# EEZ_CF-DIC_r5B6.net
KiCad netlist of a schematic drawn in EAGLE
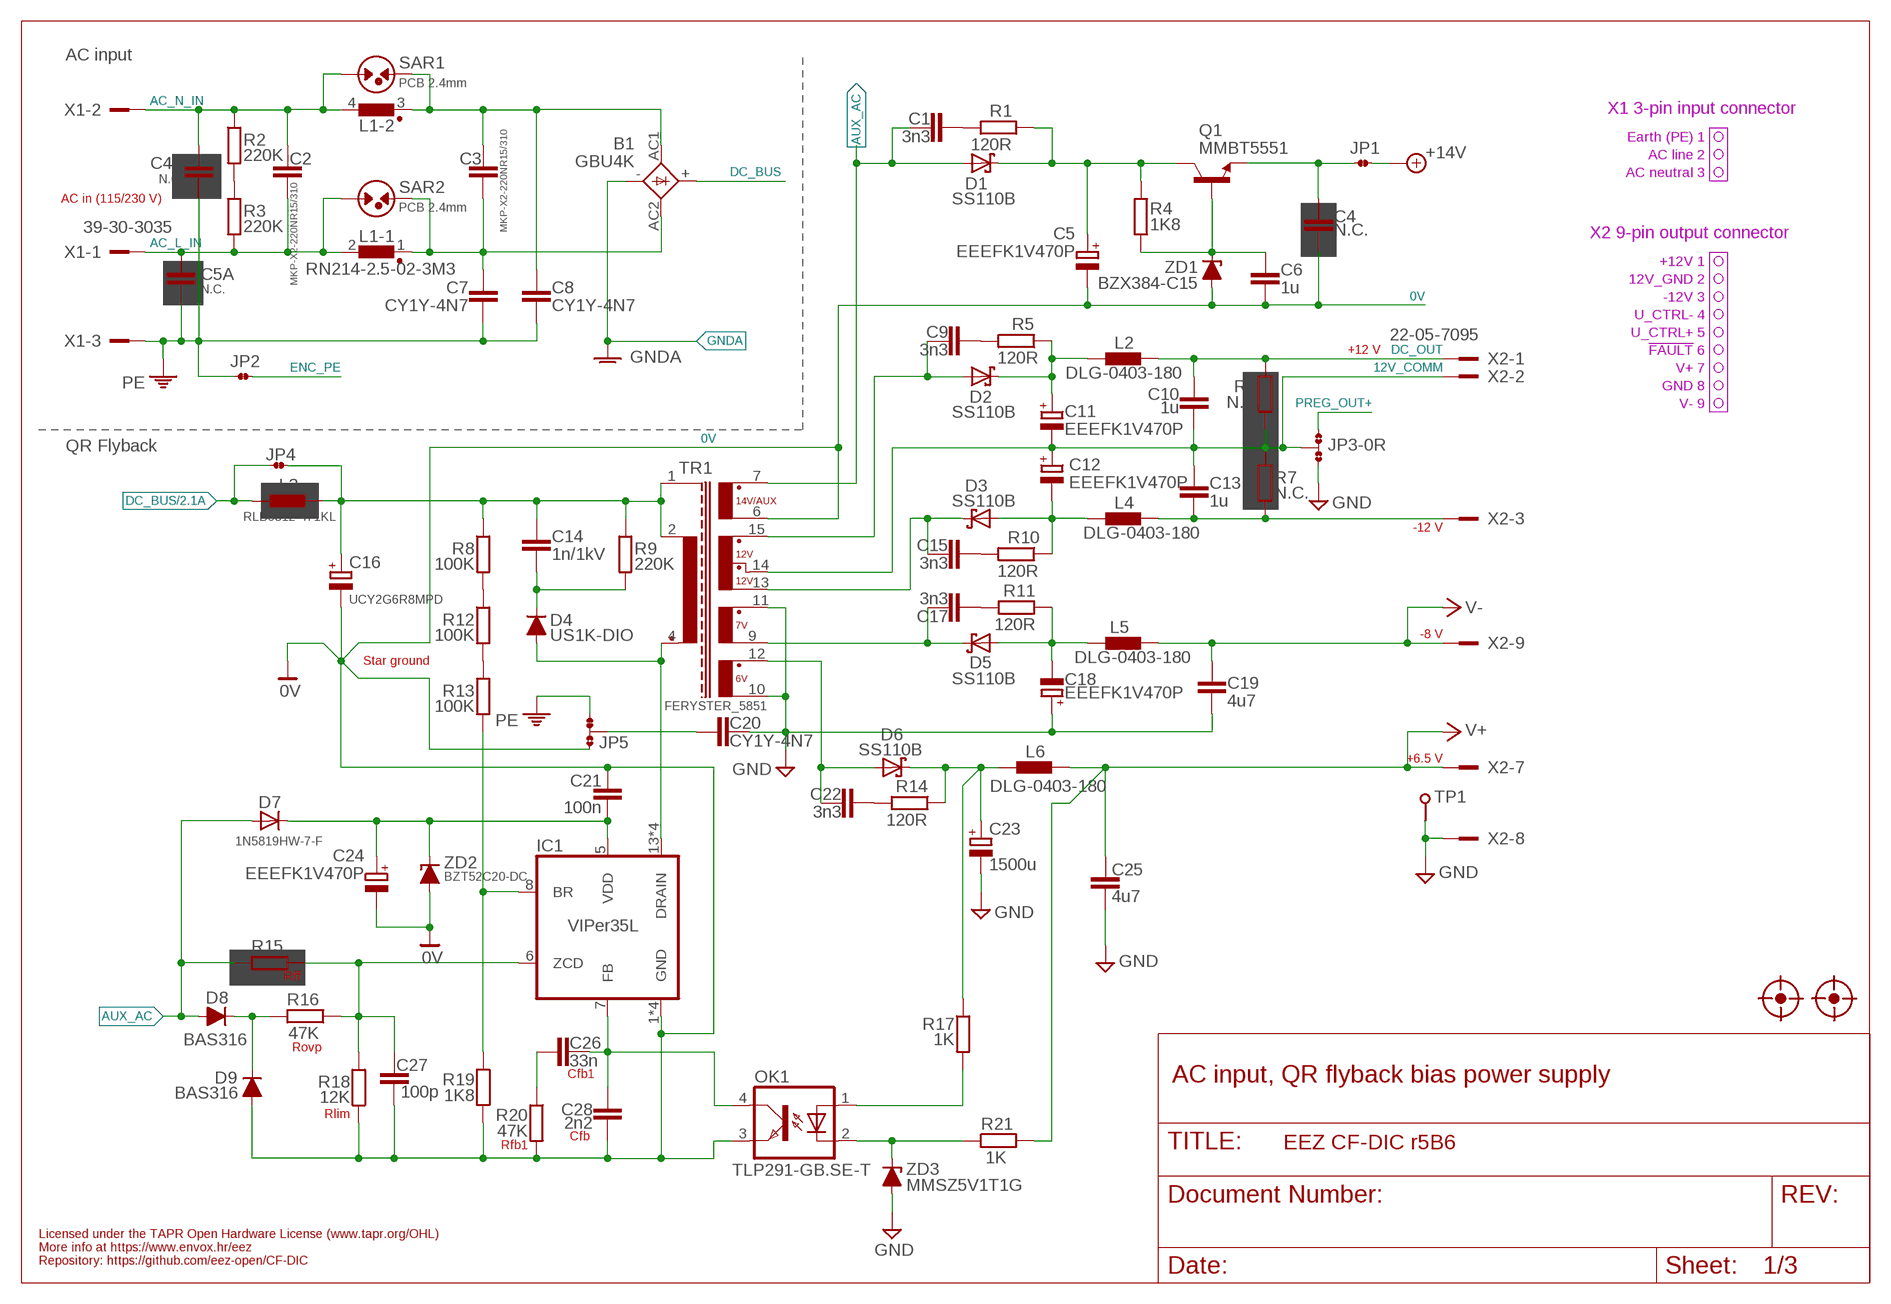
[diagram p0: schematic, sheet 1]
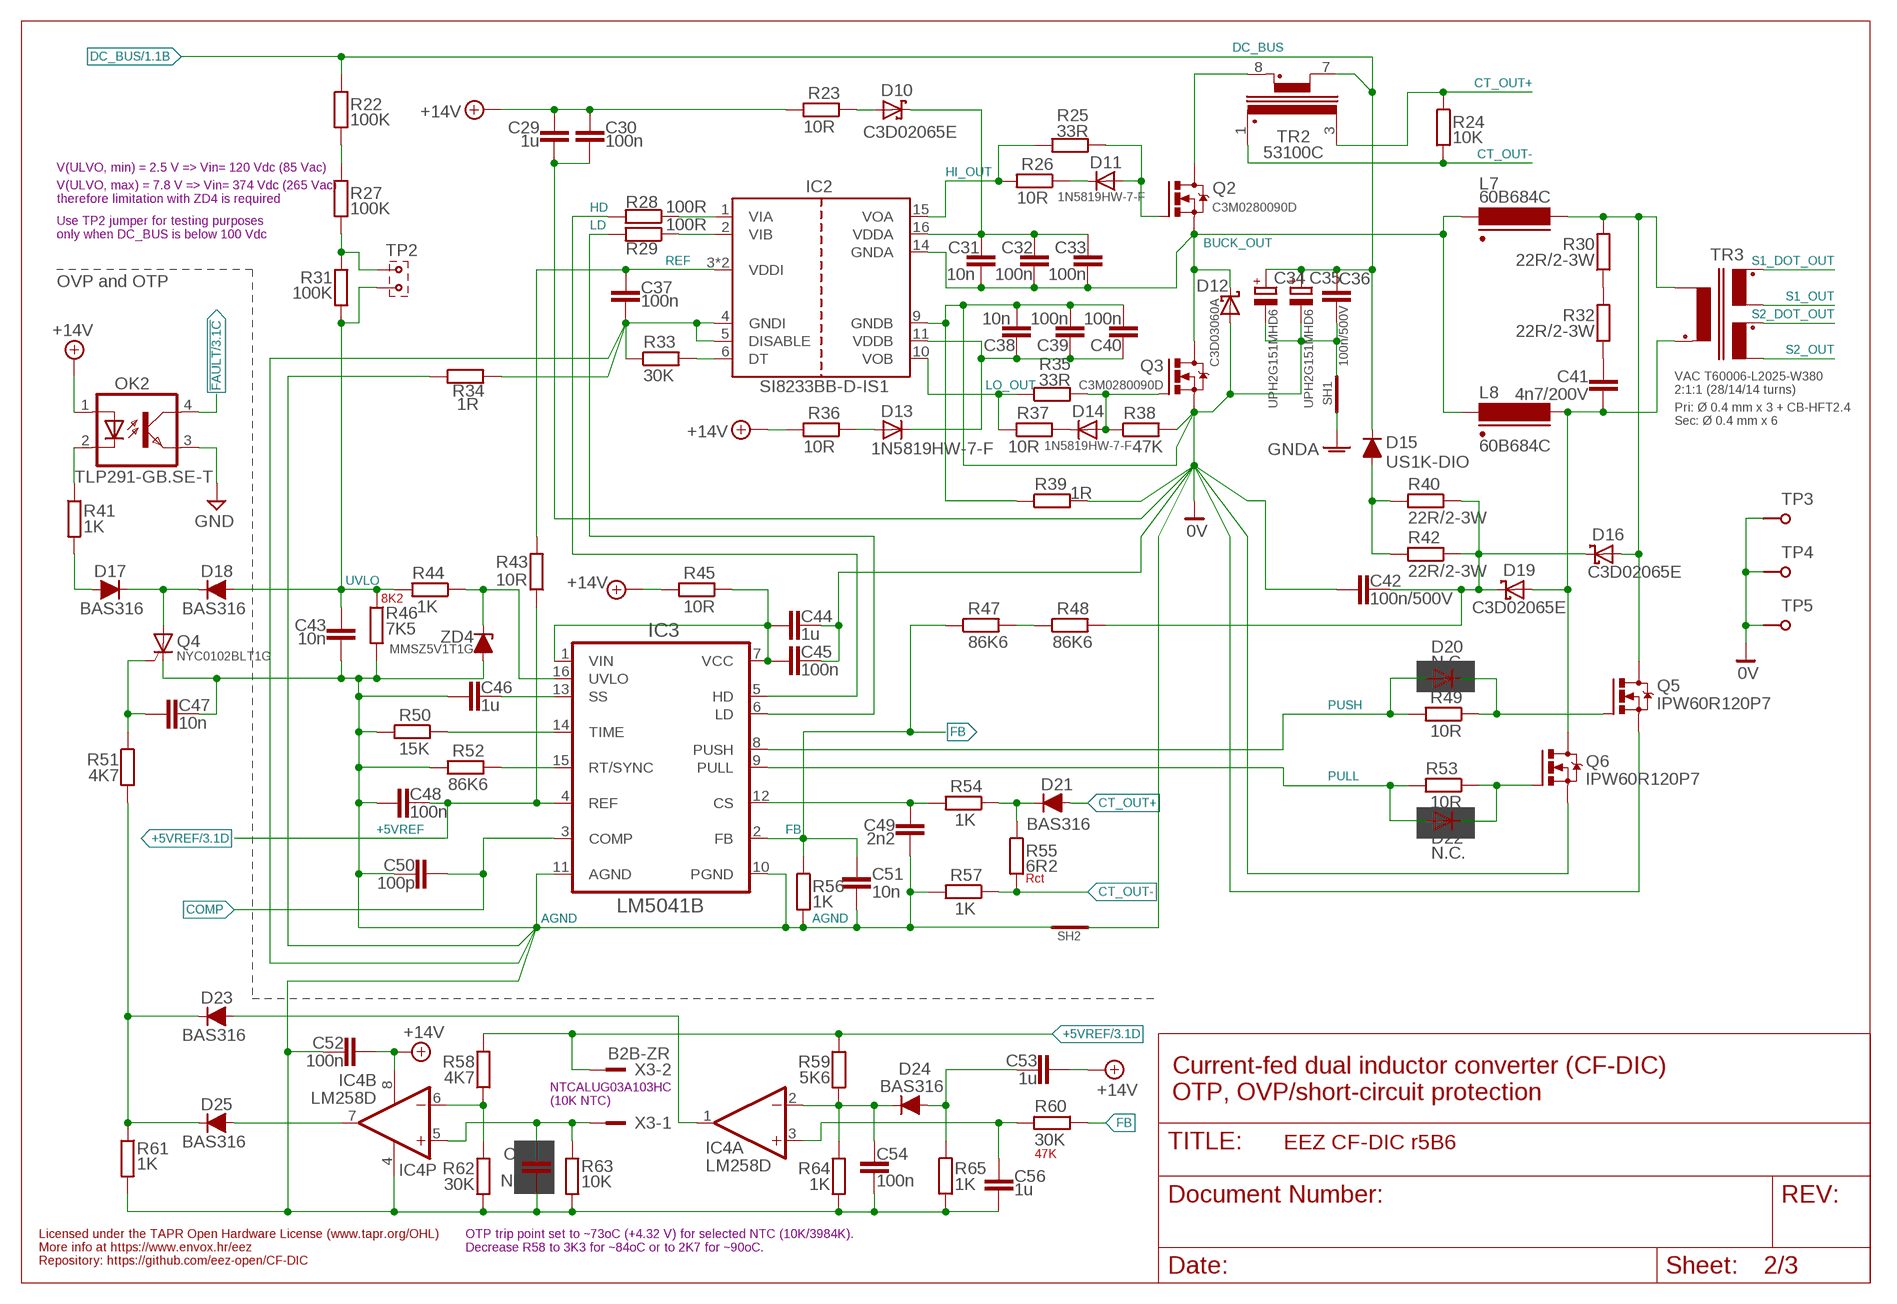
[diagram p1: schematic, sheet 2]
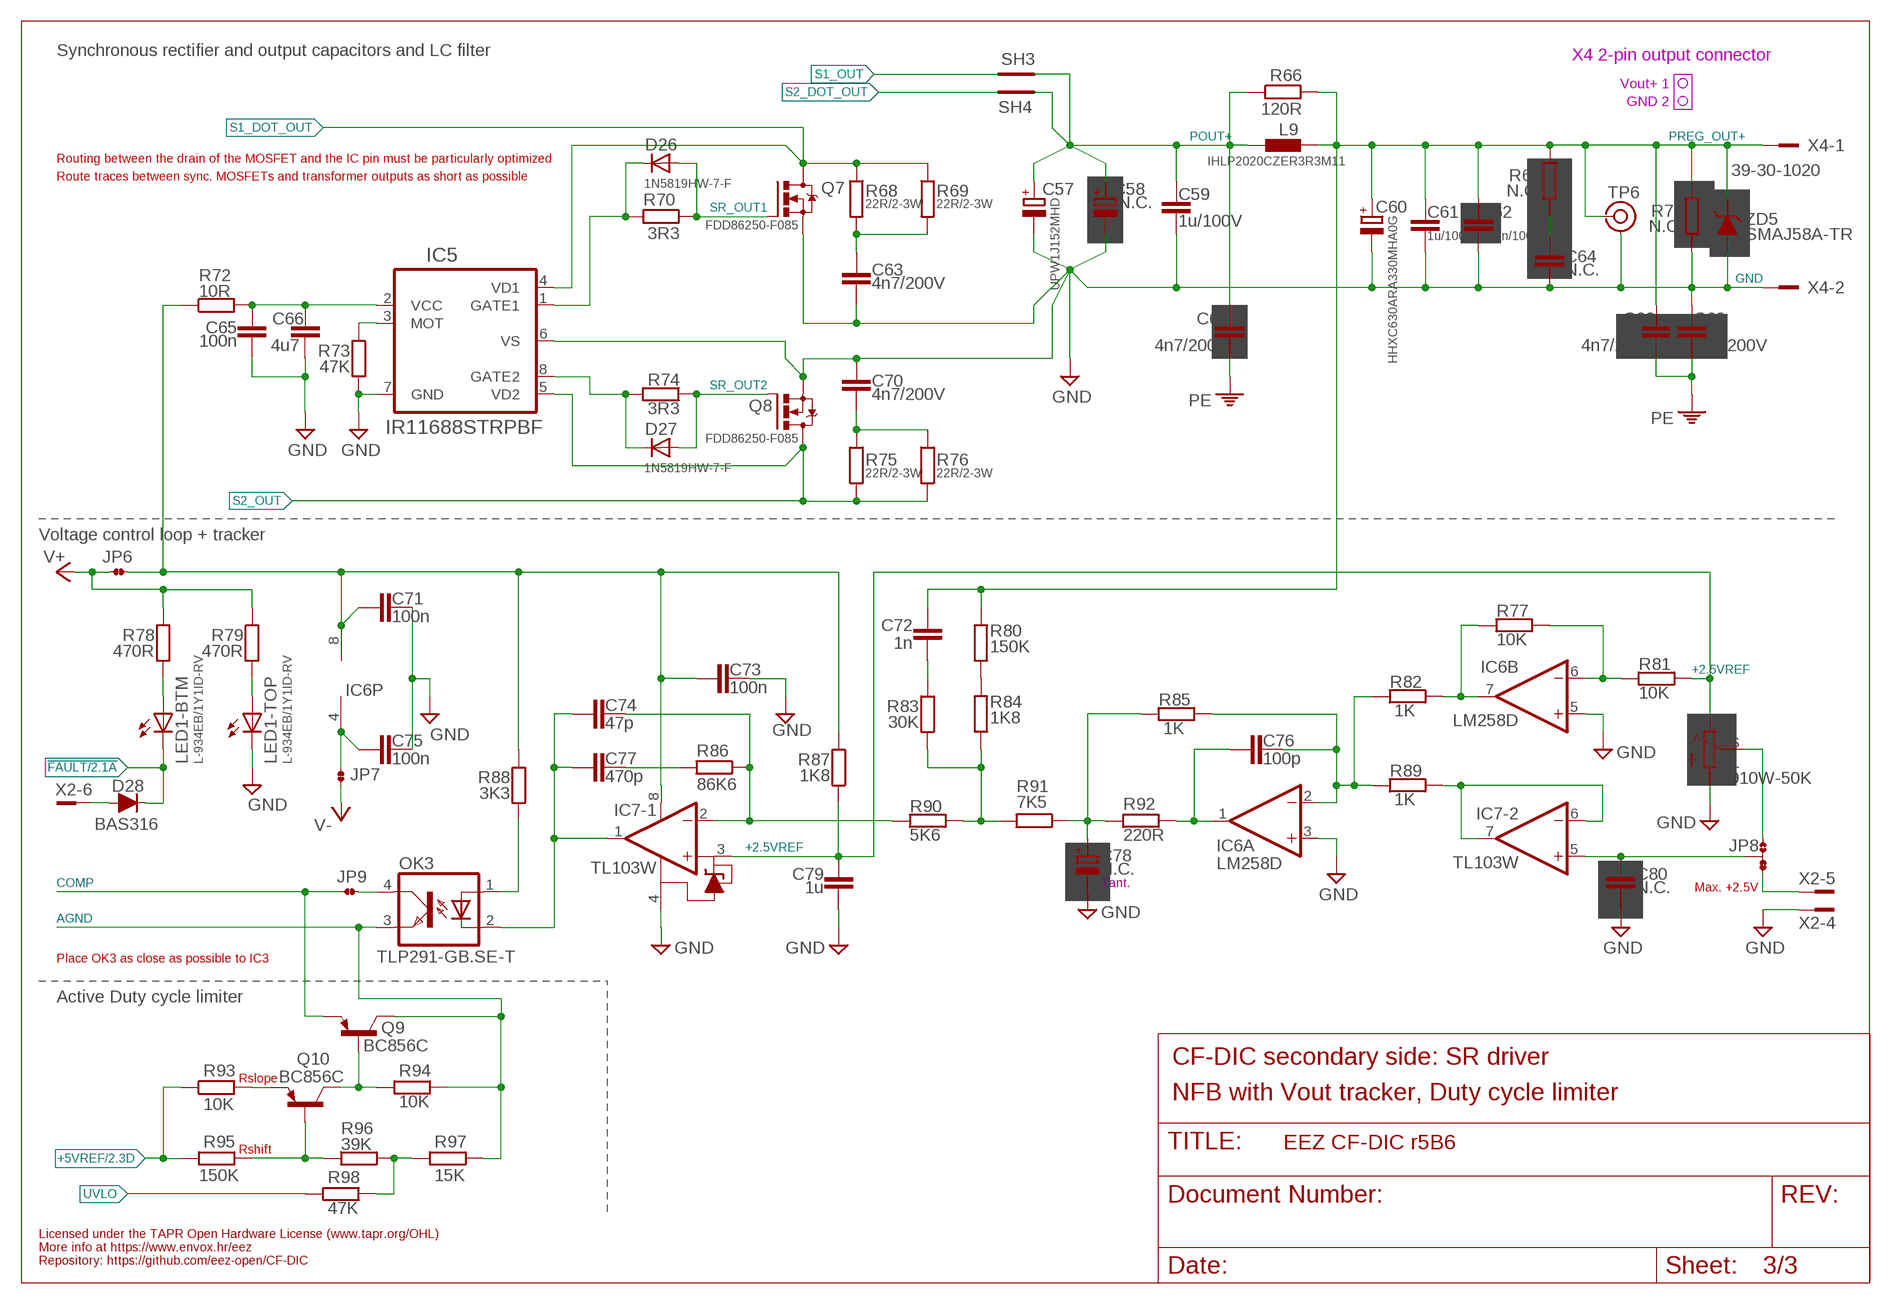
[diagram p2: schematic, sheet 3]

(export (version "E")
  (design (tool "Eeschema 10.0.6"))
  (components
    (comp (ref "B1")
      (value "GBU4K")
      (footprint "eagle-import:GBU4K_CRE")
      (libsource (lib "eagle-import") (part "BRIDGE-CREEPAGE"))
    )
    (comp (ref "C1")
      (value "3n3")
      (footprint "eagle-import:C0805")
      (libsource (lib "eagle-import") (part "C-EUC0805"))
    )
    (comp (ref "C2")
      (value "MKP-X2-220NR15/310")
      (footprint "eagle-import:C150-072X183")
      (libsource (lib "eagle-import") (part "C-EU150-072X183"))
    )
    (comp (ref "C3")
      (value "MKP-X2-220NR15/310")
      (footprint "eagle-import:C150-072X183")
      (libsource (lib "eagle-import") (part "C-EU150-072X183"))
    )
    (comp (ref "C4")
      (value "N.C.")
      (footprint "eagle-import:C0603")
      (libsource (lib "eagle-import") (part "C-EUC0603"))
    )
    (comp (ref "C4A")
      (value "N.C.")
      (footprint "eagle-import:CY075-032X103-ROTATED")
      (libsource (lib "eagle-import") (part "C-EUCY-ROTATED"))
    )
    (comp (ref "C5")
      (value "EEEFK1V470P")
      (footprint "eagle-import:CAPAE660X610N")
      (libsource (lib "eagle-import") (part "ECAPPANASONIC_H"))
    )
    (comp (ref "C5A")
      (value "N.C.")
      (footprint "eagle-import:CY075-032X103")
      (libsource (lib "eagle-import") (part "C-EUCY"))
    )
    (comp (ref "C6")
      (value "1u")
      (footprint "eagle-import:C0805")
      (libsource (lib "eagle-import") (part "C-EUC0805"))
    )
    (comp (ref "C7")
      (value "CY1Y-4N7")
      (footprint "eagle-import:CY075-032X103")
      (libsource (lib "eagle-import") (part "C-EUCY"))
    )
    (comp (ref "C8")
      (value "CY1Y-4N7")
      (footprint "eagle-import:CY075-032X103")
      (libsource (lib "eagle-import") (part "C-EUCY"))
    )
    (comp (ref "C9")
      (value "3n3")
      (footprint "eagle-import:C0805")
      (libsource (lib "eagle-import") (part "C-EUC0805"))
    )
    (comp (ref "C10")
      (value "1u")
      (footprint "eagle-import:C0805")
      (libsource (lib "eagle-import") (part "C-EUC0805"))
    )
    (comp (ref "C11")
      (value "EEEFK1V470P")
      (footprint "eagle-import:CAPAE660X610N")
      (libsource (lib "eagle-import") (part "ECAPPANASONIC_H"))
    )
    (comp (ref "C12")
      (value "EEEFK1V470P")
      (footprint "eagle-import:CAPAE660X610N")
      (libsource (lib "eagle-import") (part "ECAPPANASONIC_H"))
    )
    (comp (ref "C13")
      (value "1u")
      (footprint "eagle-import:C0805")
      (libsource (lib "eagle-import") (part "C-EUC0805"))
    )
    (comp (ref "C14")
      (value "1n/1kV")
      (footprint "eagle-import:C1210")
      (libsource (lib "eagle-import") (part "C-EUC1210"))
    )
    (comp (ref "C15")
      (value "3n3")
      (footprint "eagle-import:C0805")
      (libsource (lib "eagle-import") (part "C-EUC0805"))
    )
    (comp (ref "C16")
      (value "UCY2G6R8MPD")
      (footprint "eagle-import:ECAP5_10.5")
      (libsource (lib "eagle-import") (part "ECAP5G_10.5MM"))
    )
    (comp (ref "C17")
      (value "3n3")
      (footprint "eagle-import:C0805")
      (libsource (lib "eagle-import") (part "C-EUC0805"))
    )
    (comp (ref "C18")
      (value "EEEFK1V470P")
      (footprint "eagle-import:CAPAE660X610N")
      (libsource (lib "eagle-import") (part "ECAPPANASONIC_H"))
    )
    (comp (ref "C19")
      (value "4u7")
      (footprint "eagle-import:C1206")
      (libsource (lib "eagle-import") (part "C-EUC1206"))
    )
    (comp (ref "C20")
      (value "CY1Y-4N7")
      (footprint "eagle-import:CY075-032X103")
      (libsource (lib "eagle-import") (part "C-EUCY"))
    )
    (comp (ref "C21")
      (value "100n")
      (footprint "eagle-import:C0603")
      (libsource (lib "eagle-import") (part "C-EUC0603"))
    )
    (comp (ref "C22")
      (value "3n3")
      (footprint "eagle-import:C0805")
      (libsource (lib "eagle-import") (part "C-EUC0805"))
    )
    (comp (ref "C23")
      (value "1500u")
      (footprint "eagle-import:ECAP5_13")
      (libsource (lib "eagle-import") (part "ECAP5G_13MM"))
    )
    (comp (ref "C24")
      (value "EEEFK1V470P")
      (footprint "eagle-import:CAPAE660X610N")
      (libsource (lib "eagle-import") (part "ECAPPANASONIC_H"))
    )
    (comp (ref "C25")
      (value "4u7")
      (footprint "eagle-import:C1206")
      (libsource (lib "eagle-import") (part "C-EUC1206"))
    )
    (comp (ref "C26")
      (value "33n")
      (footprint "eagle-import:C0805")
      (libsource (lib "eagle-import") (part "C-EUC0805"))
    )
    (comp (ref "C27")
      (value "100p")
      (footprint "eagle-import:C0805")
      (libsource (lib "eagle-import") (part "C-EUC0805"))
    )
    (comp (ref "C28")
      (value "2n2")
      (footprint "eagle-import:C0805")
      (libsource (lib "eagle-import") (part "C-EUC0805"))
    )
    (comp (ref "D1")
      (value "SS110B")
      (footprint "eagle-import:SMB")
      (libsource (lib "eagle-import") (part "SCHOTTKYSMB"))
    )
    (comp (ref "D2")
      (value "SS110B")
      (footprint "eagle-import:SMB")
      (libsource (lib "eagle-import") (part "SCHOTTKYSMB"))
    )
    (comp (ref "D3")
      (value "SS110B")
      (footprint "eagle-import:SMB")
      (libsource (lib "eagle-import") (part "SCHOTTKYSMB"))
    )
    (comp (ref "D4")
      (value "US1K-DIO")
      (footprint "eagle-import:DO214AA")
      (libsource (lib "eagle-import") (part "DIODEDO214AA"))
    )
    (comp (ref "D5")
      (value "SS110B")
      (footprint "eagle-import:SMB")
      (libsource (lib "eagle-import") (part "SCHOTTKYSMB"))
    )
    (comp (ref "D6")
      (value "SS110B")
      (footprint "eagle-import:SMB")
      (libsource (lib "eagle-import") (part "SCHOTTKYSMB"))
    )
    (comp (ref "D7")
      (value "1N5819HW-7-F")
      (footprint "eagle-import:SOD323-W")
      (libsource (lib "eagle-import") (part "DIODE-SOD323-W"))
    )
    (comp (ref "D8")
      (value "BAS316")
      (footprint "eagle-import:SOD323-R")
      (libsource (lib "eagle-import") (part "DIODESOD323R"))
    )
    (comp (ref "D9")
      (value "BAS316")
      (footprint "eagle-import:SOD323-R")
      (libsource (lib "eagle-import") (part "DIODESOD323R"))
    )
    (comp (ref "FM1")
      (value "FIDUCIAL_2")
      (footprint "eagle-import:FIDUCIAL_DUAL")
      (libsource (lib "eagle-import") (part "FIDUCIAL_2"))
    )
    (comp (ref "FM2")
      (value "FIDUCIAL_2")
      (footprint "eagle-import:FIDUCIAL_DUAL")
      (libsource (lib "eagle-import") (part "FIDUCIAL_2"))
    )
    (comp (ref "IC1")
      (value "VIPer35L")
      (footprint "eagle-import:SOIC-16")
      (libsource (lib "eagle-import") (part "VIPER35"))
    )
    (comp (ref "JP1")
      (value "JP2-NOCUT")
      (footprint "eagle-import:JP2-NOCUT")
      (libsource (lib "eagle-import") (part "JP2-NOCUT"))
    )
    (comp (ref "JP2")
      (value "JP2-NOCUT")
      (footprint "eagle-import:JP2-NOCUT")
      (libsource (lib "eagle-import") (part "JP2-NOCUT"))
    )
    (comp (ref "JP3")
      (value "0R-JUMPA")
      (footprint "eagle-import:A0R-JMP")
      (libsource (lib "eagle-import") (part "0R-JUMPA"))
    )
    (comp (ref "JP4")
      (value "JP2-NOCUT")
      (footprint "eagle-import:JP2-NOCUT")
      (libsource (lib "eagle-import") (part "JP2-NOCUT"))
    )
    (comp (ref "JP5")
      (value "JP3-CUT")
      (footprint "eagle-import:JP3-CUT")
      (libsource (lib "eagle-import") (part "JP3-CUT"))
    )
    (comp (ref "L1")
      (value "RN214-2.5-02-3M3")
      (footprint "eagle-import:RN214")
      (fields (field (name "FARNELL") "1191518"))
      (libsource (lib "eagle-import") (part "EEZ_inductors_and_transformers_RN214"))
    )
    (comp (ref "L2")
      (value "DLG-0403-180")
      (footprint "eagle-import:DE0403")
      (libsource (lib "eagle-import") (part "EEZ_inductors_and_transformers_DE0403"))
    )
    (comp (ref "L3")
      (value "RLB0812-471KL")
      (footprint "eagle-import:FERSYTER_DSZ6")
      (libsource (lib "eagle-import") (part "FERYSTER_DSZ6"))
    )
    (comp (ref "L4")
      (value "DLG-0403-180")
      (footprint "eagle-import:DE0403")
      (libsource (lib "eagle-import") (part "EEZ_inductors_and_transformers_DE0403"))
    )
    (comp (ref "L5")
      (value "DLG-0403-180")
      (footprint "eagle-import:DE0403")
      (libsource (lib "eagle-import") (part "EEZ_inductors_and_transformers_DE0403"))
    )
    (comp (ref "L6")
      (value "DLG-0403-180")
      (footprint "eagle-import:DE0403")
      (libsource (lib "eagle-import") (part "EEZ_inductors_and_transformers_DE0403"))
    )
    (comp (ref "OK1")
      (value "TLP291-GB.SE-T")
      (footprint "eagle-import:SO4")
      (libsource (lib "eagle-import") (part "TLP291"))
    )
    (comp (ref "Q1")
      (value "MMBT5551")
      (footprint "eagle-import:SOT23-BEC")
      (libsource (lib "eagle-import") (part "-NPN-SOT23-BECMMBT5551LT1"))
    )
    (comp (ref "R1")
      (value "120R")
      (footprint "eagle-import:R0805")
      (libsource (lib "eagle-import") (part "R-EU_R0805"))
    )
    (comp (ref "R2")
      (value "220K")
      (footprint "eagle-import:R1206")
      (libsource (lib "eagle-import") (part "R-EU_R1206"))
    )
    (comp (ref "R3")
      (value "220K")
      (footprint "eagle-import:R1206")
      (libsource (lib "eagle-import") (part "R-EU_R1206"))
    )
    (comp (ref "R4")
      (value "1K8")
      (footprint "eagle-import:R0805")
      (libsource (lib "eagle-import") (part "R-EU_R0805"))
    )
    (comp (ref "R5")
      (value "120R")
      (footprint "eagle-import:R0805")
      (libsource (lib "eagle-import") (part "R-EU_R0805"))
    )
    (comp (ref "R6")
      (value "N.C.")
      (footprint "eagle-import:R0805")
      (libsource (lib "eagle-import") (part "R-EU_R0805"))
    )
    (comp (ref "R7")
      (value "N.C.")
      (footprint "eagle-import:R0805")
      (libsource (lib "eagle-import") (part "R-EU_R0805"))
    )
    (comp (ref "R8")
      (value "100K")
      (footprint "eagle-import:R1206")
      (libsource (lib "eagle-import") (part "R-EU_R1206"))
    )
    (comp (ref "R9")
      (value "220K")
      (footprint "eagle-import:R1206")
      (libsource (lib "eagle-import") (part "R-EU_R1206"))
    )
    (comp (ref "R10")
      (value "120R")
      (footprint "eagle-import:R0805")
      (libsource (lib "eagle-import") (part "R-EU_R0805"))
    )
    (comp (ref "R11")
      (value "120R")
      (footprint "eagle-import:R0805")
      (libsource (lib "eagle-import") (part "R-EU_R0805"))
    )
    (comp (ref "R12")
      (value "100K")
      (footprint "eagle-import:R1206")
      (libsource (lib "eagle-import") (part "R-EU_R1206"))
    )
    (comp (ref "R13")
      (value "100K")
      (footprint "eagle-import:R1206")
      (libsource (lib "eagle-import") (part "R-EU_R1206"))
    )
    (comp (ref "R14")
      (value "120R")
      (footprint "eagle-import:R0805")
      (libsource (lib "eagle-import") (part "R-EU_R0805"))
    )
    (comp (ref "R15")
      (value "N.C.")
      (footprint "eagle-import:R0805")
      (libsource (lib "eagle-import") (part "R-EU_R0805"))
    )
    (comp (ref "R16")
      (value "47K")
      (footprint "eagle-import:R0805")
      (libsource (lib "eagle-import") (part "R-EU_R0805"))
    )
    (comp (ref "R17")
      (value "1K")
      (footprint "eagle-import:R0805")
      (libsource (lib "eagle-import") (part "R-EU_R0805"))
    )
    (comp (ref "R18")
      (value "12K")
      (footprint "eagle-import:R0805")
      (libsource (lib "eagle-import") (part "R-EU_R0805"))
    )
    (comp (ref "R19")
      (value "1K8")
      (footprint "eagle-import:R0805")
      (libsource (lib "eagle-import") (part "R-EU_R0805"))
    )
    (comp (ref "R20")
      (value "47K")
      (footprint "eagle-import:R0805")
      (libsource (lib "eagle-import") (part "R-EU_R0805"))
    )
    (comp (ref "R21")
      (value "1K")
      (footprint "eagle-import:R0805")
      (libsource (lib "eagle-import") (part "R-EU_R0805"))
    )
    (comp (ref "SAR1")
      (value "PCB 2.4mm")
      (footprint "eagle-import:PCB-SAR_2.4MM")
      (libsource (lib "eagle-import") (part "SARPCB-2.4MM"))
    )
    (comp (ref "SAR2")
      (value "PCB 2.4mm")
      (footprint "eagle-import:PCB-SAR_2.4MM")
      (libsource (lib "eagle-import") (part "SARPCB-2.4MM"))
    )
    (comp (ref "TP1")
      (value "PCB_TEST_TABSHIELD")
      (footprint "eagle-import:PCB_SHIELD_TAB")
      (libsource (lib "eagle-import") (part "PCB_TEST_TABSHIELD"))
    )
    (comp (ref "TR1")
      (value "FERYSTER_5851")
      (footprint "eagle-import:FERYSTER_5572")
      (libsource (lib "eagle-import") (part "FERYSTER_5851"))
    )
    (comp (ref "X1")
      (value "39-30-3035")
      (footprint "eagle-import:MINIFIT_6659-3_CRE")
      (libsource (lib "eagle-import") (part "MINIFIT_6659-3-CRE"))
    )
    (comp (ref "X2")
      (value "22-05-7095")
      (footprint "eagle-import:SPOX_22-05-7095")
      (libsource (lib "eagle-import") (part "SPOX_22-05-7095"))
    )
    (comp (ref "ZD1")
      (value "BZX384-C15")
      (footprint "eagle-import:SOD323-W")
      (libsource (lib "eagle-import") (part "ZENER-DIODESOD323"))
    )
    (comp (ref "ZD2")
      (value "BZT52C20-DC")
      (footprint "eagle-import:SOD123")
      (libsource (lib "eagle-import") (part "ZENER-DIODESOD123"))
    )
    (comp (ref "ZD3")
      (value "MMSZ5V1T1G")
      (footprint "eagle-import:SOD323-W")
      (libsource (lib "eagle-import") (part "ZENER-DIODESOD323"))
    )
    (comp (ref "C29")
      (value "1u")
      (footprint "eagle-import:C0805")
      (libsource (lib "eagle-import") (part "C-EUC0805"))
    )
    (comp (ref "C30")
      (value "100n")
      (footprint "eagle-import:C0603")
      (libsource (lib "eagle-import") (part "C-EUC0603"))
    )
    (comp (ref "C31")
      (value "10n")
      (footprint "eagle-import:C0603")
      (libsource (lib "eagle-import") (part "C-EUC0603"))
    )
    (comp (ref "C32")
      (value "100n")
      (footprint "eagle-import:C0603")
      (libsource (lib "eagle-import") (part "C-EUC0603"))
    )
    (comp (ref "C33")
      (value "100n")
      (footprint "eagle-import:C0603")
      (libsource (lib "eagle-import") (part "C-EUC0603"))
    )
    (comp (ref "C34")
      (value "UPH2G151MHD6")
      (footprint "eagle-import:ECAP7.5_18")
      (libsource (lib "eagle-import") (part "ECAP7.5G_18MM"))
    )
    (comp (ref "C35")
      (value "UPH2G151MHD6")
      (footprint "eagle-import:ECAP7.5_18")
      (libsource (lib "eagle-import") (part "ECAP7.5G_18MM"))
    )
    (comp (ref "C36")
      (value "100n/500V")
      (footprint "eagle-import:C1812")
      (libsource (lib "eagle-import") (part "C-EUC1812"))
    )
    (comp (ref "C37")
      (value "100n")
      (footprint "eagle-import:C0603")
      (libsource (lib "eagle-import") (part "C-EUC0603"))
    )
    (comp (ref "C38")
      (value "10n")
      (footprint "eagle-import:C0603")
      (libsource (lib "eagle-import") (part "C-EUC0603"))
    )
    (comp (ref "C39")
      (value "100n")
      (footprint "eagle-import:C0603")
      (libsource (lib "eagle-import") (part "C-EUC0603"))
    )
    (comp (ref "C40")
      (value "100n")
      (footprint "eagle-import:C0603")
      (libsource (lib "eagle-import") (part "C-EUC0603"))
    )
    (comp (ref "C41")
      (value "4n7/200V")
      (footprint "eagle-import:C1210")
      (libsource (lib "eagle-import") (part "C-EUC1210"))
    )
    (comp (ref "C42")
      (value "100n/500V")
      (footprint "eagle-import:C1812")
      (libsource (lib "eagle-import") (part "C-EUC1812"))
    )
    (comp (ref "C43")
      (value "10n")
      (footprint "eagle-import:C0603")
      (libsource (lib "eagle-import") (part "C-EUC0603"))
    )
    (comp (ref "C44")
      (value "1u")
      (footprint "eagle-import:C0805")
      (libsource (lib "eagle-import") (part "C-EUC0805"))
    )
    (comp (ref "C45")
      (value "100n")
      (footprint "eagle-import:C0603")
      (libsource (lib "eagle-import") (part "C-EUC0603"))
    )
    (comp (ref "C46")
      (value "1u")
      (footprint "eagle-import:C0805")
      (libsource (lib "eagle-import") (part "C-EUC0805"))
    )
    (comp (ref "C47")
      (value "10n")
      (footprint "eagle-import:C0603")
      (libsource (lib "eagle-import") (part "C-EUC0603"))
    )
    (comp (ref "C48")
      (value "100n")
      (footprint "eagle-import:C0603")
      (libsource (lib "eagle-import") (part "C-EUC0603"))
    )
    (comp (ref "C49")
      (value "2n2")
      (footprint "eagle-import:C0805")
      (libsource (lib "eagle-import") (part "C-EUC0805"))
    )
    (comp (ref "C50")
      (value "100p")
      (footprint "eagle-import:C0805")
      (libsource (lib "eagle-import") (part "C-EUC0805"))
    )
    (comp (ref "C51")
      (value "10n")
      (footprint "eagle-import:C0603")
      (libsource (lib "eagle-import") (part "C-EUC0603"))
    )
    (comp (ref "C52")
      (value "100n")
      (footprint "eagle-import:C0603")
      (libsource (lib "eagle-import") (part "C-EUC0603"))
    )
    (comp (ref "C53")
      (value "1u")
      (footprint "eagle-import:C0805")
      (libsource (lib "eagle-import") (part "C-EUC0805"))
    )
    (comp (ref "C54")
      (value "100n")
      (footprint "eagle-import:C0603")
      (libsource (lib "eagle-import") (part "C-EUC0603"))
    )
    (comp (ref "C55")
      (value "N.C.")
      (footprint "eagle-import:C0603")
      (libsource (lib "eagle-import") (part "C-EUC0603"))
    )
    (comp (ref "C56")
      (value "1u")
      (footprint "eagle-import:C0805")
      (libsource (lib "eagle-import") (part "C-EUC0805"))
    )
    (comp (ref "D10")
      (value "C3D02065E")
      (footprint "eagle-import:TO252-L")
      (libsource (lib "eagle-import") (part "SCHOTTKY-SIC_L"))
    )
    (comp (ref "D11")
      (value "1N5819HW-7-F")
      (footprint "eagle-import:SOD323-W")
      (libsource (lib "eagle-import") (part "DIODE-SOD323-W"))
    )
    (comp (ref "D12")
      (value "C3D03060A")
      (footprint "eagle-import:TO220-2")
      (libsource (lib "eagle-import") (part "SCHOTTKY-TO220"))
    )
    (comp (ref "D13")
      (value "1N5819HW-7-F")
      (footprint "eagle-import:SOD323-W")
      (libsource (lib "eagle-import") (part "DIODE-SOD323-W"))
    )
    (comp (ref "D14")
      (value "1N5819HW-7-F")
      (footprint "eagle-import:SOD323-W")
      (libsource (lib "eagle-import") (part "DIODE-SOD323-W"))
    )
    (comp (ref "D15")
      (value "US1K-DIO")
      (footprint "eagle-import:DO214AA")
      (libsource (lib "eagle-import") (part "DIODEDO214AA"))
    )
    (comp (ref "D16")
      (value "C3D02065E")
      (footprint "eagle-import:TO252-L")
      (libsource (lib "eagle-import") (part "SCHOTTKY-SIC_L"))
    )
    (comp (ref "D17")
      (value "BAS316")
      (footprint "eagle-import:SOD323-R")
      (libsource (lib "eagle-import") (part "DIODESOD323R"))
    )
    (comp (ref "D18")
      (value "BAS316")
      (footprint "eagle-import:SOD323-R")
      (libsource (lib "eagle-import") (part "DIODESOD323R"))
    )
    (comp (ref "D19")
      (value "C3D02065E")
      (footprint "eagle-import:TO252-L")
      (libsource (lib "eagle-import") (part "SCHOTTKY-SIC_L"))
    )
    (comp (ref "D20")
      (value "N.C.")
      (footprint "eagle-import:SOD323-W")
      (libsource (lib "eagle-import") (part "DIODE-SOD323-W"))
    )
    (comp (ref "D21")
      (value "BAS316")
      (footprint "eagle-import:SOD323-R")
      (libsource (lib "eagle-import") (part "DIODESOD323R"))
    )
    (comp (ref "D22")
      (value "N.C.")
      (footprint "eagle-import:SOD323-W")
      (libsource (lib "eagle-import") (part "DIODE-SOD323-W"))
    )
    (comp (ref "D23")
      (value "BAS316")
      (footprint "eagle-import:SOD323-R")
      (libsource (lib "eagle-import") (part "DIODESOD323R"))
    )
    (comp (ref "D24")
      (value "BAS316")
      (footprint "eagle-import:SOD323-R")
      (libsource (lib "eagle-import") (part "DIODESOD323R"))
    )
    (comp (ref "D25")
      (value "BAS316")
      (footprint "eagle-import:SOD323-R")
      (libsource (lib "eagle-import") (part "DIODESOD323R"))
    )
    (comp (ref "IC2")
      (value "SI8233BB-D-IS1")
      (footprint "eagle-import:SOIC-16")
      (libsource (lib "eagle-import") (part "SI8233"))
    )
    (comp (ref "IC3")
      (value "LM5041B")
      (footprint "eagle-import:MTC16")
      (fields (field (name "MANUFACTURER_PART_NUMBER") "lm5041mtcnopb"))
      (libsource (lib "eagle-import") (part "LM5041"))
    )
    (comp (ref "IC4")
      (value "LM258D")
      (footprint "eagle-import:SOIC127P600X173-8N")
      (libsource (lib "eagle-import") (part "TL072SOIC8"))
    )
    (comp (ref "L7")
      (value "60B684C")
      (footprint "eagle-import:MURATA_6000B")
      (libsource (lib "eagle-import") (part "MURATA_6000B"))
    )
    (comp (ref "L8")
      (value "60B684C")
      (footprint "eagle-import:MURATA_6000B")
      (libsource (lib "eagle-import") (part "MURATA_6000B"))
    )
    (comp (ref "OK2")
      (value "TLP291-GB.SE-T")
      (footprint "eagle-import:SO4")
      (libsource (lib "eagle-import") (part "TLP291"))
    )
    (comp (ref "Q2")
      (value "C3M0280090D")
      (footprint "eagle-import:TO247BV")
      (libsource (lib "eagle-import") (part "IRFP240"))
    )
    (comp (ref "Q3")
      (value "C3M0280090D")
      (footprint "eagle-import:TO247BV")
      (libsource (lib "eagle-import") (part "IRFP240"))
    )
    (comp (ref "Q4")
      (value "NYC0102BLT1G")
      (footprint "eagle-import:SOT23")
      (libsource (lib "eagle-import") (part "NYC0102BLT1G"))
    )
    (comp (ref "Q5")
      (value "IPW60R120P7")
      (footprint "eagle-import:TO247BV")
      (libsource (lib "eagle-import") (part "IRFP240"))
    )
    (comp (ref "Q6")
      (value "IPW60R120P7")
      (footprint "eagle-import:TO247BV")
      (libsource (lib "eagle-import") (part "IRFP240"))
    )
    (comp (ref "R22")
      (value "100K")
      (footprint "eagle-import:R1206")
      (libsource (lib "eagle-import") (part "R-EU_R1206"))
    )
    (comp (ref "R23")
      (value "10R")
      (footprint "eagle-import:R0805")
      (libsource (lib "eagle-import") (part "R-EU_R0805"))
    )
    (comp (ref "R24")
      (value "10K")
      (footprint "eagle-import:R0805")
      (libsource (lib "eagle-import") (part "R-EU_R0805"))
    )
    (comp (ref "R25")
      (value "33R")
      (footprint "eagle-import:R0805")
      (libsource (lib "eagle-import") (part "R-EU_R0805"))
    )
    (comp (ref "R26")
      (value "10R")
      (footprint "eagle-import:R0805")
      (libsource (lib "eagle-import") (part "R-EU_R0805"))
    )
    (comp (ref "R27")
      (value "100K")
      (footprint "eagle-import:R1206")
      (libsource (lib "eagle-import") (part "R-EU_R1206"))
    )
    (comp (ref "R28")
      (value "100R")
      (footprint "eagle-import:R0805")
      (libsource (lib "eagle-import") (part "R-EU_R0805"))
    )
    (comp (ref "R29")
      (value "100R")
      (footprint "eagle-import:R0805")
      (libsource (lib "eagle-import") (part "R-EU_R0805"))
    )
    (comp (ref "R30")
      (value "22R/2-3W")
      (footprint "eagle-import:R2512")
      (libsource (lib "eagle-import") (part "R-EU_R2512"))
    )
    (comp (ref "R31")
      (value "100K")
      (footprint "eagle-import:R1206")
      (libsource (lib "eagle-import") (part "R-EU_R1206"))
    )
    (comp (ref "R32")
      (value "22R/2-3W")
      (footprint "eagle-import:R2512")
      (libsource (lib "eagle-import") (part "R-EU_R2512"))
    )
    (comp (ref "R33")
      (value "30K")
      (footprint "eagle-import:R0805")
      (libsource (lib "eagle-import") (part "R-EU_R0805"))
    )
    (comp (ref "R34")
      (value "1R")
      (footprint "eagle-import:R0805")
      (libsource (lib "eagle-import") (part "R-EU_R0805"))
    )
    (comp (ref "R35")
      (value "33R")
      (footprint "eagle-import:R0805")
      (libsource (lib "eagle-import") (part "R-EU_R0805"))
    )
    (comp (ref "R36")
      (value "10R")
      (footprint "eagle-import:R0805")
      (libsource (lib "eagle-import") (part "R-EU_R0805"))
    )
    (comp (ref "R37")
      (value "10R")
      (footprint "eagle-import:R0805")
      (libsource (lib "eagle-import") (part "R-EU_R0805"))
    )
    (comp (ref "R38")
      (value "47K")
      (footprint "eagle-import:R0805")
      (libsource (lib "eagle-import") (part "R-EU_R0805"))
    )
    (comp (ref "R39")
      (value "1R")
      (footprint "eagle-import:R0805")
      (libsource (lib "eagle-import") (part "R-EU_R0805"))
    )
    (comp (ref "R40")
      (value "22R/2-3W")
      (footprint "eagle-import:R2512")
      (libsource (lib "eagle-import") (part "R-EU_R2512"))
    )
    (comp (ref "R41")
      (value "1K")
      (footprint "eagle-import:R0805")
      (libsource (lib "eagle-import") (part "R-EU_R0805"))
    )
    (comp (ref "R42")
      (value "22R/2-3W")
      (footprint "eagle-import:R2512")
      (libsource (lib "eagle-import") (part "R-EU_R2512"))
    )
    (comp (ref "R43")
      (value "10R")
      (footprint "eagle-import:R0805")
      (libsource (lib "eagle-import") (part "R-EU_R0805"))
    )
    (comp (ref "R44")
      (value "1K")
      (footprint "eagle-import:R0805")
      (libsource (lib "eagle-import") (part "R-EU_R0805"))
    )
    (comp (ref "R45")
      (value "10R")
      (footprint "eagle-import:R0805")
      (libsource (lib "eagle-import") (part "R-EU_R0805"))
    )
    (comp (ref "R46")
      (value "7K5")
      (footprint "eagle-import:R0805")
      (libsource (lib "eagle-import") (part "R-EU_R0805"))
    )
    (comp (ref "R47")
      (value "86K6")
      (footprint "eagle-import:R0805")
      (libsource (lib "eagle-import") (part "R-EU_R0805"))
    )
    (comp (ref "R48")
      (value "86K6")
      (footprint "eagle-import:R0805")
      (libsource (lib "eagle-import") (part "R-EU_R0805"))
    )
    (comp (ref "R49")
      (value "10R")
      (footprint "eagle-import:R0805")
      (libsource (lib "eagle-import") (part "R-EU_R0805"))
    )
    (comp (ref "R50")
      (value "15K")
      (footprint "eagle-import:R0805")
      (libsource (lib "eagle-import") (part "R-EU_R0805"))
    )
    (comp (ref "R51")
      (value "4K7")
      (footprint "eagle-import:R0805")
      (libsource (lib "eagle-import") (part "R-EU_R0805"))
    )
    (comp (ref "R52")
      (value "86K6")
      (footprint "eagle-import:R0805")
      (libsource (lib "eagle-import") (part "R-EU_R0805"))
    )
    (comp (ref "R53")
      (value "10R")
      (footprint "eagle-import:R0805")
      (libsource (lib "eagle-import") (part "R-EU_R0805"))
    )
    (comp (ref "R54")
      (value "1K")
      (footprint "eagle-import:R0805")
      (libsource (lib "eagle-import") (part "R-EU_R0805"))
    )
    (comp (ref "R55")
      (value "6R2")
      (footprint "eagle-import:R0805")
      (libsource (lib "eagle-import") (part "R-EU_R0805"))
    )
    (comp (ref "R56")
      (value "1K")
      (footprint "eagle-import:R0805")
      (libsource (lib "eagle-import") (part "R-EU_R0805"))
    )
    (comp (ref "R57")
      (value "1K")
      (footprint "eagle-import:R0805")
      (libsource (lib "eagle-import") (part "R-EU_R0805"))
    )
    (comp (ref "R58")
      (value "4K7")
      (footprint "eagle-import:R0805")
      (libsource (lib "eagle-import") (part "R-EU_R0805"))
    )
    (comp (ref "R59")
      (value "5K6")
      (footprint "eagle-import:R0805")
      (libsource (lib "eagle-import") (part "R-EU_R0805"))
    )
    (comp (ref "R60")
      (value "30K")
      (footprint "eagle-import:R0805")
      (libsource (lib "eagle-import") (part "R-EU_R0805"))
    )
    (comp (ref "R61")
      (value "1K")
      (footprint "eagle-import:R0805")
      (libsource (lib "eagle-import") (part "R-EU_R0805"))
    )
    (comp (ref "R62")
      (value "30K")
      (footprint "eagle-import:R0805")
      (libsource (lib "eagle-import") (part "R-EU_R0805"))
    )
    (comp (ref "R63")
      (value "10K")
      (footprint "eagle-import:R0805")
      (libsource (lib "eagle-import") (part "R-EU_R0805"))
    )
    (comp (ref "R64")
      (value "1K")
      (footprint "eagle-import:R0805")
      (libsource (lib "eagle-import") (part "R-EU_R0805"))
    )
    (comp (ref "R65")
      (value "1K")
      (footprint "eagle-import:R0805")
      (libsource (lib "eagle-import") (part "R-EU_R0805"))
    )
    (comp (ref "SH1")
      (value "SHORTNOHOLE")
      (footprint "eagle-import:SHORT_NOHOLE")
      (libsource (lib "eagle-import") (part "SHORTNOHOLE"))
    )
    (comp (ref "SH2")
      (value "SHORTNOHOLE")
      (footprint "eagle-import:SHORT_NOHOLE")
      (libsource (lib "eagle-import") (part "SHORTNOHOLE"))
    )
    (comp (ref "TP2")
      (value "JUMPER-2PIN-2MM")
      (footprint "eagle-import:2MM-2")
      (libsource (lib "eagle-import") (part "JUMPER-2PIN-2MM"))
    )
    (comp (ref "TP3")
      (value "TEST-PIN1.2")
      (footprint "eagle-import:TEST-PIN_1.2MM")
      (libsource (lib "eagle-import") (part "TEST-PIN1.2"))
    )
    (comp (ref "TP4")
      (value "TEST-PIN1.2")
      (footprint "eagle-import:TEST-PIN_1.2MM")
      (libsource (lib "eagle-import") (part "TEST-PIN1.2"))
    )
    (comp (ref "TP5")
      (value "TEST-PIN1.2")
      (footprint "eagle-import:TEST-PIN_1.2MM")
      (libsource (lib "eagle-import") (part "TEST-PIN1.2"))
    )
    (comp (ref "TR2")
      (value "53100C")
      (footprint "eagle-import:MURATA_5300")
      (libsource (lib "eagle-import") (part "MURATA_5300"))
    )
    (comp (ref "TR3")
      (value "VAC T60006-L2025-W380")
      (footprint "eagle-import:VAC_DUAL_SEC")
      (libsource (lib "eagle-import") (part "PCB_TRAFO_FLYBACK2-VAC"))
    )
    (comp (ref "X3")
      (value "B2B-ZR")
      (footprint "eagle-import:B2B-ZR")
      (libsource (lib "eagle-import") (part "B2B-ZR"))
    )
    (comp (ref "ZD4")
      (value "MMSZ5V1T1G")
      (footprint "eagle-import:SOD323-W")
      (libsource (lib "eagle-import") (part "ZENER-DIODESOD323"))
    )
    (comp (ref "C57")
      (value "UPW1J152MHD")
      (footprint "eagle-import:ECAP7.5_18-H35.5-2A")
      (libsource (lib "eagle-import") (part "ECAPH35.5-2A"))
    )
    (comp (ref "C58")
      (value "N.C.")
      (footprint "eagle-import:ECAP7.5_18")
      (libsource (lib "eagle-import") (part "ECAP7.5G_18MM"))
    )
    (comp (ref "C59")
      (value "1u/100V")
      (footprint "eagle-import:C1206")
      (libsource (lib "eagle-import") (part "C-EUC1206"))
    )
    (comp (ref "C60")
      (value "HHXC630ARA330MHA0G")
      (footprint "eagle-import:CAPAE830X1050N")
      (libsource (lib "eagle-import") (part "ECAPSMD8.3MM/HA0"))
    )
    (comp (ref "C61")
      (value "1u/100V")
      (footprint "eagle-import:C1206")
      (libsource (lib "eagle-import") (part "C-EUC1206"))
    )
    (comp (ref "C62")
      (value "100n/100V")
      (footprint "eagle-import:C1206")
      (libsource (lib "eagle-import") (part "C-EUC1206"))
    )
    (comp (ref "C63")
      (value "4n7/200V")
      (footprint "eagle-import:C1206")
      (libsource (lib "eagle-import") (part "C-EUC1206"))
    )
    (comp (ref "C64")
      (value "N.C.")
      (footprint "eagle-import:C1206")
      (libsource (lib "eagle-import") (part "C-EUC1206"))
    )
    (comp (ref "C65")
      (value "100n")
      (footprint "eagle-import:C0603")
      (libsource (lib "eagle-import") (part "C-EUC0603"))
    )
    (comp (ref "C66")
      (value "4u7")
      (footprint "eagle-import:C1206")
      (libsource (lib "eagle-import") (part "C-EUC1206"))
    )
    (comp (ref "C67")
      (value "4n7/200V")
      (footprint "eagle-import:C1206")
      (libsource (lib "eagle-import") (part "C-EUC1206"))
    )
    (comp (ref "C68")
      (value "4n7/200V")
      (footprint "eagle-import:C1206")
      (libsource (lib "eagle-import") (part "C-EUC1206"))
    )
    (comp (ref "C69")
      (value "4n7/200V")
      (footprint "eagle-import:C1206")
      (libsource (lib "eagle-import") (part "C-EUC1206"))
    )
    (comp (ref "C70")
      (value "4n7/200V")
      (footprint "eagle-import:C1206")
      (libsource (lib "eagle-import") (part "C-EUC1206"))
    )
    (comp (ref "C71")
      (value "100n")
      (footprint "eagle-import:C0603")
      (libsource (lib "eagle-import") (part "C-EUC0603"))
    )
    (comp (ref "C72")
      (value "1n")
      (footprint "eagle-import:C0805")
      (libsource (lib "eagle-import") (part "C-EUC0805"))
    )
    (comp (ref "C73")
      (value "100n")
      (footprint "eagle-import:C0603")
      (libsource (lib "eagle-import") (part "C-EUC0603"))
    )
    (comp (ref "C74")
      (value "47p")
      (footprint "eagle-import:C0805")
      (libsource (lib "eagle-import") (part "C-EUC0805"))
    )
    (comp (ref "C75")
      (value "100n")
      (footprint "eagle-import:C0603")
      (libsource (lib "eagle-import") (part "C-EUC0603"))
    )
    (comp (ref "C76")
      (value "100p")
      (footprint "eagle-import:C0805")
      (libsource (lib "eagle-import") (part "C-EUC0805"))
    )
    (comp (ref "C77")
      (value "470p")
      (footprint "eagle-import:C0805")
      (libsource (lib "eagle-import") (part "C-EUC0805"))
    )
    (comp (ref "C78")
      (value "N.C.")
      (footprint "eagle-import:EC1206")
      (libsource (lib "eagle-import") (part "ECAP1206"))
    )
    (comp (ref "C79")
      (value "1u")
      (footprint "eagle-import:C0805")
      (libsource (lib "eagle-import") (part "C-EUC0805"))
    )
    (comp (ref "C80")
      (value "N.C.")
      (footprint "eagle-import:C0805")
      (libsource (lib "eagle-import") (part "C-EUC0805"))
    )
    (comp (ref "D26")
      (value "1N5819HW-7-F")
      (footprint "eagle-import:SOD323-W")
      (libsource (lib "eagle-import") (part "DIODE-SOD323-W"))
    )
    (comp (ref "D27")
      (value "1N5819HW-7-F")
      (footprint "eagle-import:SOD323-W")
      (libsource (lib "eagle-import") (part "DIODE-SOD323-W"))
    )
    (comp (ref "D28")
      (value "BAS316")
      (footprint "eagle-import:SOD323-R")
      (libsource (lib "eagle-import") (part "DIODESOD323R"))
    )
    (comp (ref "IC5")
      (value "IR11688STRPBF")
      (footprint "eagle-import:SO8")
      (libsource (lib "eagle-import") (part "IR11688"))
    )
    (comp (ref "IC6")
      (value "LM258D")
      (footprint "eagle-import:SOIC127P600X173-8N")
      (libsource (lib "eagle-import") (part "TL072SOIC8"))
    )
    (comp (ref "IC7")
      (value "TL103W")
      (footprint "eagle-import:SOIC127P600X173-8N")
      (libsource (lib "eagle-import") (part "TL103W"))
    )
    (comp (ref "JP6")
      (value "JP2-NOCUT")
      (footprint "eagle-import:JP2-NOCUT")
      (libsource (lib "eagle-import") (part "JP2-NOCUT"))
    )
    (comp (ref "JP7")
      (value "JP2-NOCUT")
      (footprint "eagle-import:JP2-NOCUT")
      (libsource (lib "eagle-import") (part "JP2-NOCUT"))
    )
    (comp (ref "JP8")
      (value "JP3-CUT")
      (footprint "eagle-import:JP3-CUT")
      (libsource (lib "eagle-import") (part "JP3-CUT"))
    )
    (comp (ref "JP9")
      (value "JP2-NOCUT")
      (footprint "eagle-import:JP2-NOCUT")
      (libsource (lib "eagle-import") (part "JP2-NOCUT"))
    )
    (comp (ref "L9")
      (value "IHLP2020CZER3R3M11")
      (footprint "eagle-import:IHLP-2020BZ-11")
      (libsource (lib "eagle-import") (part "EEZ_inductors_and_transformers_IHLP-2020BZ-11"))
    )
    (comp (ref "LED1")
      (value "L-934EB/1Y1ID-RV")
      (footprint "eagle-import:L-934EB")
      (libsource (lib "eagle-import") (part "LED_L-934EB/1Y1ID-RV"))
    )
    (comp (ref "OK3")
      (value "TLP291-GB.SE-T")
      (footprint "eagle-import:SO4")
      (libsource (lib "eagle-import") (part "TLP291"))
    )
    (comp (ref "P1")
      (value "T910W-50K")
      (footprint "eagle-import:S64W")
      (libsource (lib "eagle-import") (part "TPOT-S64W"))
    )
    (comp (ref "Q7")
      (value "FDD86250-F085")
      (footprint "eagle-import:TO263")
      (libsource (lib "eagle-import") (part "N-MOSFETTO263"))
    )
    (comp (ref "Q8")
      (value "FDD86250-F085")
      (footprint "eagle-import:TO263")
      (libsource (lib "eagle-import") (part "N-MOSFETTO263"))
    )
    (comp (ref "Q9")
      (value "BC856C")
      (footprint "eagle-import:SOT23-BEC")
      (libsource (lib "eagle-import") (part "-PNP-SOT23-BECBC857C"))
    )
    (comp (ref "Q10")
      (value "BC856C")
      (footprint "eagle-import:SOT23-BEC")
      (libsource (lib "eagle-import") (part "-PNP-SOT23-BECBC857C"))
    )
    (comp (ref "R66")
      (value "120R")
      (footprint "eagle-import:R0805")
      (libsource (lib "eagle-import") (part "R-EU_R0805"))
    )
    (comp (ref "R67")
      (value "N.C.")
      (footprint "eagle-import:R1210")
      (libsource (lib "eagle-import") (part "R-EU_R1210"))
    )
    (comp (ref "R68")
      (value "22R/2-3W")
      (footprint "eagle-import:R2512")
      (libsource (lib "eagle-import") (part "R-EU_R2512"))
    )
    (comp (ref "R69")
      (value "22R/2-3W")
      (footprint "eagle-import:R2512")
      (libsource (lib "eagle-import") (part "R-EU_R2512"))
    )
    (comp (ref "R70")
      (value "3R3")
      (footprint "eagle-import:R0805")
      (libsource (lib "eagle-import") (part "R-EU_R0805"))
    )
    (comp (ref "R71")
      (value "N.C.")
      (footprint "eagle-import:R2512")
      (libsource (lib "eagle-import") (part "R-EU_R2512"))
    )
    (comp (ref "R72")
      (value "10R")
      (footprint "eagle-import:R0805")
      (libsource (lib "eagle-import") (part "R-EU_R0805"))
    )
    (comp (ref "R73")
      (value "47K")
      (footprint "eagle-import:R0805")
      (libsource (lib "eagle-import") (part "R-EU_R0805"))
    )
    (comp (ref "R74")
      (value "3R3")
      (footprint "eagle-import:R0805")
      (libsource (lib "eagle-import") (part "R-EU_R0805"))
    )
    (comp (ref "R75")
      (value "22R/2-3W")
      (footprint "eagle-import:R2512")
      (libsource (lib "eagle-import") (part "R-EU_R2512"))
    )
    (comp (ref "R76")
      (value "22R/2-3W")
      (footprint "eagle-import:R2512")
      (libsource (lib "eagle-import") (part "R-EU_R2512"))
    )
    (comp (ref "R77")
      (value "10K")
      (footprint "eagle-import:R0805")
      (libsource (lib "eagle-import") (part "R-EU_R0805"))
    )
    (comp (ref "R78")
      (value "470R")
      (footprint "eagle-import:R0805")
      (libsource (lib "eagle-import") (part "R-EU_R0805"))
    )
    (comp (ref "R79")
      (value "470R")
      (footprint "eagle-import:R0805")
      (libsource (lib "eagle-import") (part "R-EU_R0805"))
    )
    (comp (ref "R80")
      (value "150K")
      (footprint "eagle-import:R0805")
      (libsource (lib "eagle-import") (part "R-EU_R0805"))
    )
    (comp (ref "R81")
      (value "10K")
      (footprint "eagle-import:R0805")
      (libsource (lib "eagle-import") (part "R-EU_R0805"))
    )
    (comp (ref "R82")
      (value "1K")
      (footprint "eagle-import:R0805")
      (libsource (lib "eagle-import") (part "R-EU_R0805"))
    )
    (comp (ref "R83")
      (value "30K")
      (footprint "eagle-import:R0805")
      (libsource (lib "eagle-import") (part "R-EU_R0805"))
    )
    (comp (ref "R84")
      (value "1K8")
      (footprint "eagle-import:R0805")
      (libsource (lib "eagle-import") (part "R-EU_R0805"))
    )
    (comp (ref "R85")
      (value "1K")
      (footprint "eagle-import:R0805")
      (libsource (lib "eagle-import") (part "R-EU_R0805"))
    )
    (comp (ref "R86")
      (value "86K6")
      (footprint "eagle-import:R0805")
      (libsource (lib "eagle-import") (part "R-EU_R0805"))
    )
    (comp (ref "R87")
      (value "1K8")
      (footprint "eagle-import:R0805")
      (libsource (lib "eagle-import") (part "R-EU_R0805"))
    )
    (comp (ref "R88")
      (value "3K3")
      (footprint "eagle-import:R0805")
      (libsource (lib "eagle-import") (part "R-EU_R0805"))
    )
    (comp (ref "R89")
      (value "1K")
      (footprint "eagle-import:R0805")
      (libsource (lib "eagle-import") (part "R-EU_R0805"))
    )
    (comp (ref "R90")
      (value "5K6")
      (footprint "eagle-import:R0805")
      (libsource (lib "eagle-import") (part "R-EU_R0805"))
    )
    (comp (ref "R91")
      (value "7K5")
      (footprint "eagle-import:R0805")
      (libsource (lib "eagle-import") (part "R-EU_R0805"))
    )
    (comp (ref "R92")
      (value "220R")
      (footprint "eagle-import:R0805")
      (libsource (lib "eagle-import") (part "R-EU_R0805"))
    )
    (comp (ref "R93")
      (value "10K")
      (footprint "eagle-import:R0805")
      (libsource (lib "eagle-import") (part "R-EU_R0805"))
    )
    (comp (ref "R94")
      (value "10K")
      (footprint "eagle-import:R0805")
      (libsource (lib "eagle-import") (part "R-EU_R0805"))
    )
    (comp (ref "R95")
      (value "150K")
      (footprint "eagle-import:R0805")
      (libsource (lib "eagle-import") (part "R-EU_R0805"))
    )
    (comp (ref "R96")
      (value "39K")
      (footprint "eagle-import:R0805")
      (libsource (lib "eagle-import") (part "R-EU_R0805"))
    )
    (comp (ref "R97")
      (value "15K")
      (footprint "eagle-import:R0805")
      (libsource (lib "eagle-import") (part "R-EU_R0805"))
    )
    (comp (ref "R98")
      (value "47K")
      (footprint "eagle-import:R0805")
      (libsource (lib "eagle-import") (part "R-EU_R0805"))
    )
    (comp (ref "SH3")
      (value "SHORTNOHOLE")
      (footprint "eagle-import:SHORT_NOHOLE")
      (libsource (lib "eagle-import") (part "SHORTNOHOLE"))
    )
    (comp (ref "SH4")
      (value "SHORTNOHOLE")
      (footprint "eagle-import:SHORT_NOHOLE")
      (libsource (lib "eagle-import") (part "SHORTNOHOLE"))
    )
    (comp (ref "TP6")
      (value "TEST_POINT-2")
      (footprint "eagle-import:TP_1.1MM_2")
      (libsource (lib "eagle-import") (part "TEST_POINT-2"))
    )
    (comp (ref "X4")
      (value "39-30-1020")
      (footprint "eagle-import:MINIFIT_39301020")
      (libsource (lib "eagle-import") (part "MINIFIT_39301020"))
    )
    (comp (ref "ZD5")
      (value "SMAJ58A-TR")
      (footprint "eagle-import:DO214AC")
      (libsource (lib "eagle-import") (part "PSMAXX"))
    )
  )
  (nets
    (net (code "1") (name "+2.5VREF") (class "Default")
      (node (ref "C79") (pin "1") (pinfunction "1_1") (pintype "passive"))
      (node (ref "IC7") (pin "3") (pinfunction "+IN1_3") (pintype "input"))
      (node (ref "P1") (pin "E") (pinfunction "E_E") (pintype "passive"))
      (node (ref "R81") (pin "2") (pinfunction "2_2") (pintype "passive"))
      (node (ref "R87") (pin "1") (pinfunction "1_1") (pintype "passive"))
    )
    (net (code "2") (name "+5VREF") (class "Default")
      (node (ref "C48") (pin "2") (pinfunction "2_2") (pintype "passive"))
      (node (ref "IC3") (pin "4") (pinfunction "REF_4") (pintype "output"))
      (node (ref "R43") (pin "1") (pinfunction "1_1") (pintype "passive"))
      (node (ref "R58") (pin "2") (pinfunction "2_2") (pintype "passive"))
      (node (ref "R59") (pin "2") (pinfunction "2_2") (pintype "passive"))
      (node (ref "R93") (pin "1") (pinfunction "1_1") (pintype "passive"))
      (node (ref "R95") (pin "1") (pinfunction "1_1") (pintype "passive"))
      (node (ref "X3") (pin "2") (pinfunction "1_2") (pintype "passive"))
    )
    (net (code "3") (name "+14V") (class "Default")
      (node (ref "C29") (pin "2") (pinfunction "2_2") (pintype "passive"))
      (node (ref "C30") (pin "2") (pinfunction "2_2") (pintype "passive"))
      (node (ref "C52") (pin "1") (pinfunction "1_1") (pintype "passive"))
      (node (ref "C53") (pin "1") (pinfunction "1_1") (pintype "passive"))
      (node (ref "IC4") (pin "8") (pinfunction "V+_8") (pintype "power_in"))
      (node (ref "JP1") (pin "2") (pinfunction "2_2") (pintype "passive"))
      (node (ref "OK2") (pin "1") (pinfunction "A_1") (pintype "passive"))
      (node (ref "R23") (pin "2") (pinfunction "2_2") (pintype "passive"))
      (node (ref "R36") (pin "2") (pinfunction "2_2") (pintype "passive"))
      (node (ref "R45") (pin "2") (pinfunction "2_2") (pintype "passive"))
    )
    (net (code "4") (name "0V") (class "Default")
      (node (ref "C16") (pin "-") (pinfunction "-_-") (pintype "passive"))
      (node (ref "C21") (pin "1") (pinfunction "1_1") (pintype "passive"))
      (node (ref "C24") (pin "2") (pinfunction "-_2") (pintype "passive"))
      (node (ref "C27") (pin "2") (pinfunction "2_2") (pintype "passive"))
      (node (ref "C28") (pin "2") (pinfunction "2_2") (pintype "passive"))
      (node (ref "C29") (pin "1") (pinfunction "1_1") (pintype "passive"))
      (node (ref "C30") (pin "1") (pinfunction "1_1") (pintype "passive"))
      (node (ref "C34") (pin "-") (pinfunction "-_-") (pintype "passive"))
      (node (ref "C35") (pin "-") (pinfunction "-_-") (pintype "passive"))
      (node (ref "C36") (pin "2") (pinfunction "2_2") (pintype "passive"))
      (node (ref "C38") (pin "2") (pinfunction "2_2") (pintype "passive"))
      (node (ref "C39") (pin "2") (pinfunction "2_2") (pintype "passive"))
      (node (ref "C4") (pin "2") (pinfunction "2_2") (pintype "passive"))
      (node (ref "C40") (pin "2") (pinfunction "2_2") (pintype "passive"))
      (node (ref "C42") (pin "1") (pinfunction "1_1") (pintype "passive"))
      (node (ref "C44") (pin "2") (pinfunction "2_2") (pintype "passive"))
      (node (ref "C45") (pin "2") (pinfunction "2_2") (pintype "passive"))
      (node (ref "C5") (pin "2") (pinfunction "-_2") (pintype "passive"))
      (node (ref "C6") (pin "2") (pinfunction "2_2") (pintype "passive"))
      (node (ref "D12") (pin "2") (pinfunction "A_2") (pintype "passive"))
      (node (ref "D9") (pin "A") (pinfunction "A_A") (pintype "passive"))
      (node (ref "IC1") (pin "1") (pinfunction "GND_1") (pintype "passive"))
      (node (ref "IC1") (pin "2") (pinfunction "GND_2") (pintype "passive"))
      (node (ref "IC1") (pin "3") (pinfunction "GND_3") (pintype "passive"))
      (node (ref "IC1") (pin "4") (pinfunction "GND_4") (pintype "passive"))
      (node (ref "IC2") (pin "9") (pinfunction "GNDB_9") (pintype "power_in"))
      (node (ref "JP5") (pin "NO") (pinfunction "NO_NO") (pintype "passive"))
      (node (ref "OK1") (pin "3") (pinfunction "EMIT_3") (pintype "passive"))
      (node (ref "Q3") (pin "S") (pinfunction "S_S") (pintype "passive"))
      (node (ref "Q5") (pin "S") (pinfunction "S_S") (pintype "passive"))
      (node (ref "Q6") (pin "S") (pinfunction "S_S") (pintype "passive"))
      (node (ref "R18") (pin "1") (pinfunction "1_1") (pintype "passive"))
      (node (ref "R19") (pin "2") (pinfunction "2_2") (pintype "passive"))
      (node (ref "R20") (pin "2") (pinfunction "2_2") (pintype "passive"))
      (node (ref "R38") (pin "2") (pinfunction "2_2") (pintype "passive"))
      (node (ref "R39") (pin "1") (pinfunction "1_1") (pintype "passive"))
      (node (ref "R39") (pin "2") (pinfunction "2_2") (pintype "passive"))
      (node (ref "SH1") (pin "P$2") (pinfunction "GND_B_P$2") (pintype "bidirectional"))
      (node (ref "SH2") (pin "P$1") (pinfunction "GND_A_P$1") (pintype "bidirectional"))
      (node (ref "TP3") (pin "1") (pinfunction "P$1_1") (pintype "bidirectional"))
      (node (ref "TP4") (pin "1") (pinfunction "P$1_1") (pintype "bidirectional"))
      (node (ref "TP5") (pin "1") (pinfunction "P$1_1") (pintype "bidirectional"))
      (node (ref "TR1") (pin "6") (pinfunction "S_AUX_6") (pintype "passive"))
      (node (ref "ZD1") (pin "A") (pinfunction "A_A") (pintype "passive"))
      (node (ref "ZD2") (pin "A") (pinfunction "A_A") (pintype "passive"))
    )
    (net (code "5") (name "12V_COMM") (class "Default")
      (node (ref "C10") (pin "2") (pinfunction "2_2") (pintype "passive"))
      (node (ref "C11") (pin "2") (pinfunction "-_2") (pintype "passive"))
      (node (ref "C12") (pin "1") (pinfunction "+_1") (pintype "passive"))
      (node (ref "C13") (pin "1") (pinfunction "1_1") (pintype "passive"))
      (node (ref "JP3") (pin "2") (pinfunction "2_2") (pintype "passive"))
      (node (ref "R6") (pin "2") (pinfunction "2_2") (pintype "passive"))
      (node (ref "R7") (pin "1") (pinfunction "1_1") (pintype "passive"))
      (node (ref "TR1") (pin "14") (pinfunction "12V_DOT_14") (pintype "passive"))
      (node (ref "X2") (pin "2") (pinfunction "1_2") (pintype "passive"))
    )
    (net (code "6") (name "AC_L_IN") (class "Default")
      (node (ref "C2") (pin "2") (pinfunction "2_2") (pintype "passive"))
      (node (ref "C5A") (pin "2") (pinfunction "2_2") (pintype "passive"))
      (node (ref "L1") (pin "2") (pinfunction "2_2") (pintype "passive"))
      (node (ref "R3") (pin "2") (pinfunction "2_2") (pintype "passive"))
      (node (ref "SAR2") (pin "1") (pinfunction "P$1_1") (pintype "bidirectional"))
      (node (ref "X1") (pin "1") (pinfunction "1_1") (pintype "passive"))
    )
    (net (code "7") (name "AC_N_IN") (class "Default")
      (node (ref "C2") (pin "1") (pinfunction "1_1") (pintype "passive"))
      (node (ref "C4A") (pin "2") (pinfunction "2_2") (pintype "passive"))
      (node (ref "L1") (pin "4") (pinfunction "2_4") (pintype "passive"))
      (node (ref "R2") (pin "1") (pinfunction "1_1") (pintype "passive"))
      (node (ref "SAR1") (pin "1") (pinfunction "P$1_1") (pintype "bidirectional"))
      (node (ref "X1") (pin "2") (pinfunction "1_2") (pintype "passive"))
    )
    (net (code "8") (name "AGND") (class "Default")
      (node (ref "C37") (pin "1") (pinfunction "1_1") (pintype "passive"))
      (node (ref "C43") (pin "2") (pinfunction "2_2") (pintype "passive"))
      (node (ref "C46") (pin "1") (pinfunction "1_1") (pintype "passive"))
      (node (ref "C47") (pin "2") (pinfunction "2_2") (pintype "passive"))
      (node (ref "C48") (pin "1") (pinfunction "1_1") (pintype "passive"))
      (node (ref "C49") (pin "1") (pinfunction "1_1") (pintype "passive"))
      (node (ref "C50") (pin "1") (pinfunction "1_1") (pintype "passive"))
      (node (ref "C51") (pin "2") (pinfunction "2_2") (pintype "passive"))
      (node (ref "C52") (pin "2") (pinfunction "2_2") (pintype "passive"))
      (node (ref "C54") (pin "2") (pinfunction "2_2") (pintype "passive"))
      (node (ref "C55") (pin "1") (pinfunction "1_1") (pintype "passive"))
      (node (ref "C56") (pin "1") (pinfunction "1_1") (pintype "passive"))
      (node (ref "IC2") (pin "4") (pinfunction "GNDI_4") (pintype "power_in"))
      (node (ref "IC2") (pin "5") (pinfunction "DISABLE_5") (pintype "input"))
      (node (ref "IC3") (pin "10") (pinfunction "PGND_10") (pintype "power_in"))
      (node (ref "IC3") (pin "11") (pinfunction "AGND_11") (pintype "power_in"))
      (node (ref "IC4") (pin "4") (pinfunction "V-_4") (pintype "power_in"))
      (node (ref "OK3") (pin "3") (pinfunction "EMIT_3") (pintype "passive"))
      (node (ref "Q4") (pin "1") (pinfunction "C_1") (pintype "passive"))
      (node (ref "Q9") (pin "C") (pinfunction "C_C") (pintype "passive"))
      (node (ref "R33") (pin "1") (pinfunction "1_1") (pintype "passive"))
      (node (ref "R34") (pin "1") (pinfunction "1_1") (pintype "passive"))
      (node (ref "R34") (pin "2") (pinfunction "2_2") (pintype "passive"))
      (node (ref "R46") (pin "2") (pinfunction "2_2") (pintype "passive"))
      (node (ref "R50") (pin "2") (pinfunction "2_2") (pintype "passive"))
      (node (ref "R52") (pin "2") (pinfunction "2_2") (pintype "passive"))
      (node (ref "R56") (pin "2") (pinfunction "2_2") (pintype "passive"))
      (node (ref "R57") (pin "2") (pinfunction "2_2") (pintype "passive"))
      (node (ref "R61") (pin "2") (pinfunction "2_2") (pintype "passive"))
      (node (ref "R62") (pin "2") (pinfunction "2_2") (pintype "passive"))
      (node (ref "R63") (pin "2") (pinfunction "2_2") (pintype "passive"))
      (node (ref "R64") (pin "2") (pinfunction "2_2") (pintype "passive"))
      (node (ref "R65") (pin "2") (pinfunction "2_2") (pintype "passive"))
      (node (ref "R94") (pin "2") (pinfunction "2_2") (pintype "passive"))
      (node (ref "R97") (pin "2") (pinfunction "2_2") (pintype "passive"))
      (node (ref "SH2") (pin "P$2") (pinfunction "GND_B_P$2") (pintype "bidirectional"))
      (node (ref "ZD4") (pin "A") (pinfunction "A_A") (pintype "passive"))
    )
    (net (code "9") (name "AUX_AC") (class "Default")
      (node (ref "C1") (pin "2") (pinfunction "2_2") (pintype "passive"))
      (node (ref "D1") (pin "A") (pinfunction "A_A") (pintype "passive"))
      (node (ref "D7") (pin "A") (pinfunction "A_A") (pintype "passive"))
      (node (ref "D8") (pin "A") (pinfunction "A_A") (pintype "passive"))
      (node (ref "R15") (pin "2") (pinfunction "2_2") (pintype "passive"))
      (node (ref "TR1") (pin "7") (pinfunction "S_AUX_DOT_7") (pintype "passive"))
    )
    (net (code "10") (name "BUCK_OUT") (class "Default")
      (node (ref "C31") (pin "2") (pinfunction "2_2") (pintype "passive"))
      (node (ref "C32") (pin "2") (pinfunction "2_2") (pintype "passive"))
      (node (ref "C33") (pin "2") (pinfunction "2_2") (pintype "passive"))
      (node (ref "D12") (pin "1") (pinfunction "C_1") (pintype "passive"))
      (node (ref "IC2") (pin "14") (pinfunction "GNDA_14") (pintype "power_in"))
      (node (ref "L7") (pin "2") (pinfunction "P$2_2") (pintype "bidirectional"))
      (node (ref "L8") (pin "2") (pinfunction "P$2_2") (pintype "bidirectional"))
      (node (ref "Q2") (pin "S") (pinfunction "S_S") (pintype "passive"))
      (node (ref "Q3") (pin "D") (pinfunction "D_D") (pintype "passive"))
    )
    (net (code "11") (name "COMP") (class "Default")
      (node (ref "C50") (pin "2") (pinfunction "2_2") (pintype "passive"))
      (node (ref "IC3") (pin "3") (pinfunction "COMP_3") (pintype "passive"))
      (node (ref "JP9") (pin "1") (pinfunction "1_1") (pintype "passive"))
      (node (ref "Q9") (pin "E") (pinfunction "E_E") (pintype "passive"))
    )
    (net (code "12") (name "CT_OUT+") (class "Default")
      (node (ref "D21") (pin "A") (pinfunction "A_A") (pintype "passive"))
      (node (ref "R24") (pin "1") (pinfunction "1_1") (pintype "passive"))
      (node (ref "TR2") (pin "3") (pinfunction "S_3") (pintype "passive"))
    )
    (net (code "13") (name "CT_OUT-") (class "Default")
      (node (ref "R24") (pin "2") (pinfunction "2_2") (pintype "passive"))
      (node (ref "R55") (pin "2") (pinfunction "2_2") (pintype "passive"))
      (node (ref "R57") (pin "1") (pinfunction "1_1") (pintype "passive"))
      (node (ref "TR2") (pin "1") (pinfunction "S_DOT_1") (pintype "passive"))
    )
    (net (code "14") (name "DC_BUS") (class "Default")
      (node (ref "B1") (pin "+") (pinfunction "+_+") (pintype "passive"))
      (node (ref "C34") (pin "+") (pinfunction "+_+") (pintype "passive"))
      (node (ref "C35") (pin "+") (pinfunction "+_+") (pintype "passive"))
      (node (ref "C36") (pin "1") (pinfunction "1_1") (pintype "passive"))
      (node (ref "D15") (pin "C") (pinfunction "C_C") (pintype "passive"))
      (node (ref "JP4") (pin "1") (pinfunction "1_1") (pintype "passive"))
      (node (ref "L3") (pin "P$1") (pinfunction "1_P$1") (pintype "passive"))
      (node (ref "R22") (pin "1") (pinfunction "1_1") (pintype "passive"))
      (node (ref "TR2") (pin "7") (pinfunction "P_7") (pintype "passive"))
    )
    (net (code "15") (name "DC_OUT") (class "Default")
      (node (ref "C10") (pin "1") (pinfunction "1_1") (pintype "passive"))
      (node (ref "L2") (pin "2") (pinfunction "2_2") (pintype "passive"))
      (node (ref "R6") (pin "1") (pinfunction "1_1") (pintype "passive"))
      (node (ref "X2") (pin "1") (pinfunction "1_1") (pintype "passive"))
    )
    (net (code "16") (name "ENC_PE") (class "Default")
      (node (ref "JP2") (pin "2") (pinfunction "2_2") (pintype "passive"))
    )
    (net (code "17") (name "FB") (class "Default")
      (node (ref "C51") (pin "1") (pinfunction "1_1") (pintype "passive"))
      (node (ref "IC3") (pin "2") (pinfunction "FB_2") (pintype "input"))
      (node (ref "R47") (pin "1") (pinfunction "1_1") (pintype "passive"))
      (node (ref "R56") (pin "1") (pinfunction "1_1") (pintype "passive"))
      (node (ref "R60") (pin "1") (pinfunction "1_1") (pintype "passive"))
    )
    (net (code "18") (name "GND") (class "Default")
      (node (ref "C18") (pin "1") (pinfunction "+_1") (pintype "passive"))
      (node (ref "C19") (pin "1") (pinfunction "1_1") (pintype "passive"))
      (node (ref "C20") (pin "2") (pinfunction "2_2") (pintype "passive"))
      (node (ref "C23") (pin "-") (pinfunction "-_-") (pintype "passive"))
      (node (ref "C25") (pin "2") (pinfunction "2_2") (pintype "passive"))
      (node (ref "C57") (pin "-") (pinfunction "-_-") (pintype "passive"))
      (node (ref "C58") (pin "-") (pinfunction "-_-") (pintype "passive"))
      (node (ref "C59") (pin "2") (pinfunction "2_2") (pintype "passive"))
      (node (ref "C60") (pin "-") (pinfunction "-_-") (pintype "passive"))
      (node (ref "C61") (pin "2") (pinfunction "2_2") (pintype "passive"))
      (node (ref "C62") (pin "2") (pinfunction "2_2") (pintype "passive"))
      (node (ref "C63") (pin "2") (pinfunction "2_2") (pintype "passive"))
      (node (ref "C64") (pin "1") (pinfunction "1_1") (pintype "passive"))
      (node (ref "C65") (pin "2") (pinfunction "2_2") (pintype "passive"))
      (node (ref "C66") (pin "2") (pinfunction "2_2") (pintype "passive"))
      (node (ref "C69") (pin "1") (pinfunction "1_1") (pintype "passive"))
      (node (ref "C70") (pin "2") (pinfunction "2_2") (pintype "passive"))
      (node (ref "C71") (pin "2") (pinfunction "2_2") (pintype "passive"))
      (node (ref "C73") (pin "2") (pinfunction "2_2") (pintype "passive"))
      (node (ref "C75") (pin "2") (pinfunction "2_2") (pintype "passive"))
      (node (ref "C78") (pin "-") (pinfunction "-_-") (pintype "passive"))
      (node (ref "C79") (pin "2") (pinfunction "2_2") (pintype "passive"))
      (node (ref "C80") (pin "2") (pinfunction "2_2") (pintype "passive"))
      (node (ref "IC5") (pin "6") (pinfunction "VS_6") (pintype "passive"))
      (node (ref "IC5") (pin "7") (pinfunction "GND_7") (pintype "power_in"))
      (node (ref "IC6") (pin "3") (pinfunction "+IN_3") (pintype "input"))
      (node (ref "IC6") (pin "5") (pinfunction "+IN_5") (pintype "input"))
      (node (ref "IC7") (pin "4") (pinfunction "VCC-_4") (pintype "power_in"))
      (node (ref "JP3") (pin "3") (pinfunction "3_3") (pintype "passive"))
      (node (ref "LED1") (pin "TC") (pinfunction "C_TC") (pintype "passive"))
      (node (ref "OK2") (pin "3") (pinfunction "EMIT_3") (pintype "passive"))
      (node (ref "P1") (pin "A") (pinfunction "A_A") (pintype "passive"))
      (node (ref "Q7") (pin "2") (pinfunction "S_2") (pintype "passive"))
      (node (ref "Q8") (pin "2") (pinfunction "S_2") (pintype "passive"))
      (node (ref "R71") (pin "1") (pinfunction "1_1") (pintype "passive"))
      (node (ref "R73") (pin "2") (pinfunction "2_2") (pintype "passive"))
      (node (ref "TP1") (pin "1") (pinfunction "P$1_1") (pintype "bidirectional"))
      (node (ref "TP6") (pin "GND") (pinfunction "GND_GND") (pintype "bidirectional"))
      (node (ref "TR1") (pin "10") (pinfunction "6V_10") (pintype "passive"))
      (node (ref "TR1") (pin "11") (pinfunction "7V_DOT_11") (pintype "passive"))
      (node (ref "X2") (pin "4") (pinfunction "1_4") (pintype "passive"))
      (node (ref "X2") (pin "8") (pinfunction "1_8") (pintype "passive"))
      (node (ref "X4") (pin "2") (pinfunction "1_2") (pintype "passive"))
      (node (ref "ZD3") (pin "A") (pinfunction "A_A") (pintype "passive"))
      (node (ref "ZD5") (pin "A") (pinfunction "A_A") (pintype "passive"))
    )
    (net (code "19") (name "GNDA") (class "Default")
      (node (ref "B1") (pin "-") (pinfunction "-_-") (pintype "passive"))
      (node (ref "SH1") (pin "P$1") (pinfunction "GND_A_P$1") (pintype "bidirectional"))
    )
    (net (code "20") (name "HD") (class "Default")
      (node (ref "IC3") (pin "5") (pinfunction "HD_5") (pintype "output"))
      (node (ref "R28") (pin "2") (pinfunction "2_2") (pintype "passive"))
    )
    (net (code "21") (name "HI_OUT") (class "Default")
      (node (ref "IC2") (pin "15") (pinfunction "VOA_15") (pintype "output"))
      (node (ref "R25") (pin "2") (pinfunction "2_2") (pintype "passive"))
      (node (ref "R26") (pin "2") (pinfunction "2_2") (pintype "passive"))
    )
    (net (code "22") (name "LD") (class "Default")
      (node (ref "IC3") (pin "6") (pinfunction "LD_6") (pintype "output"))
      (node (ref "R29") (pin "2") (pinfunction "2_2") (pintype "passive"))
    )
    (net (code "23") (name "LO_OUT") (class "Default")
      (node (ref "IC2") (pin "10") (pinfunction "VOB_10") (pintype "output"))
      (node (ref "R35") (pin "1") (pinfunction "1_1") (pintype "passive"))
      (node (ref "R37") (pin "1") (pinfunction "1_1") (pintype "passive"))
    )
    (net (code "24") (name "Net-(C1-Pad1)") (class "Default")
      (node (ref "C1") (pin "1") (pinfunction "1_1") (pintype "passive"))
      (node (ref "R1") (pin "2") (pinfunction "2_2") (pintype "passive"))
    )
    (net (code "25") (name "Net-(C4-Pad1)") (class "Default")
      (node (ref "C4") (pin "1") (pinfunction "1_1") (pintype "passive"))
      (node (ref "JP1") (pin "1") (pinfunction "1_1") (pintype "passive"))
      (node (ref "Q1") (pin "E") (pinfunction "E_E") (pintype "passive"))
    )
    (net (code "26") (name "Net-(C5-+)") (class "Default")
      (node (ref "C5") (pin "1") (pinfunction "+_1") (pintype "passive"))
      (node (ref "D1") (pin "C") (pinfunction "C_C") (pintype "passive"))
      (node (ref "Q1") (pin "C") (pinfunction "C_C") (pintype "passive"))
      (node (ref "R1") (pin "1") (pinfunction "1_1") (pintype "passive"))
      (node (ref "R4") (pin "1") (pinfunction "1_1") (pintype "passive"))
    )
    (net (code "27") (name "Net-(C6-Pad1)") (class "Default")
      (node (ref "C6") (pin "1") (pinfunction "1_1") (pintype "passive"))
      (node (ref "Q1") (pin "B") (pinfunction "B_B") (pintype "passive"))
      (node (ref "R4") (pin "2") (pinfunction "2_2") (pintype "passive"))
      (node (ref "ZD1") (pin "C") (pinfunction "C_C") (pintype "passive"))
    )
    (net (code "28") (name "Net-(C9-Pad1)") (class "Default")
      (node (ref "C9") (pin "1") (pinfunction "1_1") (pintype "passive"))
      (node (ref "R5") (pin "2") (pinfunction "2_2") (pintype "passive"))
    )
    (net (code "29") (name "Net-(C11-+)") (class "Default")
      (node (ref "C11") (pin "1") (pinfunction "+_1") (pintype "passive"))
      (node (ref "D2") (pin "C") (pinfunction "C_C") (pintype "passive"))
      (node (ref "L2") (pin "1") (pinfunction "1_1") (pintype "passive"))
      (node (ref "R5") (pin "1") (pinfunction "1_1") (pintype "passive"))
    )
    (net (code "30") (name "Net-(C12--)") (class "Default")
      (node (ref "C12") (pin "2") (pinfunction "-_2") (pintype "passive"))
      (node (ref "D3") (pin "A") (pinfunction "A_A") (pintype "passive"))
      (node (ref "L4") (pin "1") (pinfunction "1_1") (pintype "passive"))
      (node (ref "R10") (pin "1") (pinfunction "1_1") (pintype "passive"))
    )
    (net (code "31") (name "Net-(C14-Pad2)") (class "Default")
      (node (ref "C14") (pin "2") (pinfunction "2_2") (pintype "passive"))
      (node (ref "D4") (pin "C") (pinfunction "C_C") (pintype "passive"))
      (node (ref "R9") (pin "2") (pinfunction "2_2") (pintype "passive"))
    )
    (net (code "32") (name "Net-(C15-Pad1)") (class "Default")
      (node (ref "C15") (pin "1") (pinfunction "1_1") (pintype "passive"))
      (node (ref "R10") (pin "2") (pinfunction "2_2") (pintype "passive"))
    )
    (net (code "33") (name "Net-(C17-Pad1)") (class "Default")
      (node (ref "C17") (pin "1") (pinfunction "1_1") (pintype "passive"))
      (node (ref "R11") (pin "2") (pinfunction "2_2") (pintype "passive"))
    )
    (net (code "34") (name "Net-(C18--)") (class "Default")
      (node (ref "C18") (pin "2") (pinfunction "-_2") (pintype "passive"))
      (node (ref "D5") (pin "A") (pinfunction "A_A") (pintype "passive"))
      (node (ref "L5") (pin "1") (pinfunction "1_1") (pintype "passive"))
      (node (ref "R11") (pin "1") (pinfunction "1_1") (pintype "passive"))
    )
    (net (code "35") (name "Net-(C20-Pad1)") (class "Default")
      (node (ref "C20") (pin "1") (pinfunction "1_1") (pintype "passive"))
      (node (ref "JP5") (pin "COM") (pinfunction "COM_COM") (pintype "passive"))
    )
    (net (code "36") (name "Net-(C22-Pad1)") (class "Default")
      (node (ref "C22") (pin "1") (pinfunction "1_1") (pintype "passive"))
      (node (ref "R14") (pin "2") (pinfunction "2_2") (pintype "passive"))
    )
    (net (code "37") (name "Net-(C23-Pad+)") (class "Default")
      (node (ref "C23") (pin "+") (pinfunction "+_+") (pintype "passive"))
      (node (ref "D6") (pin "C") (pinfunction "C_C") (pintype "passive"))
      (node (ref "L6") (pin "1") (pinfunction "1_1") (pintype "passive"))
      (node (ref "R14") (pin "1") (pinfunction "1_1") (pintype "passive"))
      (node (ref "R17") (pin "1") (pinfunction "1_1") (pintype "passive"))
    )
    (net (code "38") (name "Net-(C24-+)") (class "Default")
      (node (ref "C21") (pin "2") (pinfunction "2_2") (pintype "passive"))
      (node (ref "C24") (pin "1") (pinfunction "+_1") (pintype "passive"))
      (node (ref "D7") (pin "C") (pinfunction "C_C") (pintype "passive"))
      (node (ref "IC1") (pin "5") (pinfunction "VDD_5") (pintype "power_in"))
      (node (ref "ZD2") (pin "C") (pinfunction "C_C") (pintype "passive"))
    )
    (net (code "39") (name "Net-(C26-Pad1)") (class "Default")
      (node (ref "C26") (pin "1") (pinfunction "1_1") (pintype "passive"))
      (node (ref "R20") (pin "1") (pinfunction "1_1") (pintype "passive"))
    )
    (net (code "40") (name "Net-(C41-Pad1)") (class "Default")
      (node (ref "C41") (pin "1") (pinfunction "1_1") (pintype "passive"))
      (node (ref "R32") (pin "1") (pinfunction "1_1") (pintype "passive"))
    )
    (net (code "41") (name "Net-(C42-Pad2)") (class "Default")
      (node (ref "C42") (pin "2") (pinfunction "2_2") (pintype "passive"))
      (node (ref "D16") (pin "1") (pinfunction "C_1") (pintype "passive"))
      (node (ref "D16") (pin "3") (pinfunction "C_3") (pintype "passive"))
      (node (ref "D19") (pin "1") (pinfunction "C_1") (pintype "passive"))
      (node (ref "D19") (pin "3") (pinfunction "C_3") (pintype "passive"))
      (node (ref "R40") (pin "1") (pinfunction "1_1") (pintype "passive"))
      (node (ref "R42") (pin "1") (pinfunction "1_1") (pintype "passive"))
      (node (ref "R48") (pin "2") (pinfunction "2_2") (pintype "passive"))
    )
    (net (code "42") (name "Net-(C53-Pad2)") (class "Default")
      (node (ref "C53") (pin "2") (pinfunction "2_2") (pintype "passive"))
      (node (ref "D24") (pin "A") (pinfunction "A_A") (pintype "passive"))
      (node (ref "R65") (pin "1") (pinfunction "1_1") (pintype "passive"))
    )
    (net (code "43") (name "Net-(C63-Pad1)") (class "Default")
      (node (ref "C63") (pin "1") (pinfunction "1_1") (pintype "passive"))
      (node (ref "R68") (pin "2") (pinfunction "2_2") (pintype "passive"))
      (node (ref "R69") (pin "2") (pinfunction "2_2") (pintype "passive"))
    )
    (net (code "44") (name "Net-(C64-Pad2)") (class "Default")
      (node (ref "C64") (pin "2") (pinfunction "2_2") (pintype "passive"))
      (node (ref "R67") (pin "1") (pinfunction "1_1") (pintype "passive"))
    )
    (net (code "45") (name "Net-(C70-Pad1)") (class "Default")
      (node (ref "C70") (pin "1") (pinfunction "1_1") (pintype "passive"))
      (node (ref "R75") (pin "2") (pinfunction "2_2") (pintype "passive"))
      (node (ref "R76") (pin "2") (pinfunction "2_2") (pintype "passive"))
    )
    (net (code "46") (name "Net-(C72-Pad2)") (class "Default")
      (node (ref "C72") (pin "2") (pinfunction "2_2") (pintype "passive"))
      (node (ref "R83") (pin "2") (pinfunction "2_2") (pintype "passive"))
    )
    (net (code "47") (name "Net-(C77-Pad2)") (class "Default")
      (node (ref "C77") (pin "2") (pinfunction "2_2") (pintype "passive"))
      (node (ref "R86") (pin "2") (pinfunction "2_2") (pintype "passive"))
    )
    (net (code "48") (name "Net-(C78-Pad+)") (class "Default")
      (node (ref "C78") (pin "+") (pinfunction "+_+") (pintype "passive"))
      (node (ref "R85") (pin "1") (pinfunction "1_1") (pintype "passive"))
      (node (ref "R91") (pin "1") (pinfunction "1_1") (pintype "passive"))
      (node (ref "R92") (pin "1") (pinfunction "1_1") (pintype "passive"))
    )
    (net (code "49") (name "Net-(D8-PadC)") (class "Default")
      (node (ref "D8") (pin "C") (pinfunction "C_C") (pintype "passive"))
      (node (ref "D9") (pin "C") (pinfunction "C_C") (pintype "passive"))
      (node (ref "R16") (pin "2") (pinfunction "2_2") (pintype "passive"))
    )
    (net (code "50") (name "Net-(D10-A)") (class "Default")
      (node (ref "D10") (pin "2") (pinfunction "A_2") (pintype "passive"))
      (node (ref "R23") (pin "1") (pinfunction "1_1") (pintype "passive"))
    )
    (net (code "51") (name "Net-(D11-PadA)") (class "Default")
      (node (ref "D11") (pin "A") (pinfunction "A_A") (pintype "passive"))
      (node (ref "Q2") (pin "G") (pinfunction "G_G") (pintype "passive"))
      (node (ref "R25") (pin "1") (pinfunction "1_1") (pintype "passive"))
    )
    (net (code "52") (name "Net-(D11-PadC)") (class "Default")
      (node (ref "D11") (pin "C") (pinfunction "C_C") (pintype "passive"))
      (node (ref "R26") (pin "1") (pinfunction "1_1") (pintype "passive"))
    )
    (net (code "53") (name "Net-(D13-PadA)") (class "Default")
      (node (ref "D13") (pin "A") (pinfunction "A_A") (pintype "passive"))
      (node (ref "R36") (pin "1") (pinfunction "1_1") (pintype "passive"))
    )
    (net (code "54") (name "Net-(D14-PadA)") (class "Default")
      (node (ref "D14") (pin "A") (pinfunction "A_A") (pintype "passive"))
      (node (ref "Q3") (pin "G") (pinfunction "G_G") (pintype "passive"))
      (node (ref "R35") (pin "2") (pinfunction "2_2") (pintype "passive"))
      (node (ref "R38") (pin "1") (pinfunction "1_1") (pintype "passive"))
    )
    (net (code "55") (name "Net-(D14-PadC)") (class "Default")
      (node (ref "D14") (pin "C") (pinfunction "C_C") (pintype "passive"))
      (node (ref "R37") (pin "2") (pinfunction "2_2") (pintype "passive"))
    )
    (net (code "56") (name "Net-(D15-PadA)") (class "Default")
      (node (ref "D15") (pin "A") (pinfunction "A_A") (pintype "passive"))
      (node (ref "R40") (pin "2") (pinfunction "2_2") (pintype "passive"))
      (node (ref "R42") (pin "2") (pinfunction "2_2") (pintype "passive"))
    )
    (net (code "57") (name "Net-(D16-A)") (class "Default")
      (node (ref "D16") (pin "2") (pinfunction "A_2") (pintype "passive"))
      (node (ref "L7") (pin "1") (pinfunction "P$1_1") (pintype "bidirectional"))
      (node (ref "Q5") (pin "D") (pinfunction "D_D") (pintype "passive"))
      (node (ref "R30") (pin "2") (pinfunction "2_2") (pintype "passive"))
      (node (ref "TR3") (pin "P1") (pinfunction "P_P1") (pintype "passive"))
    )
    (net (code "58") (name "Net-(D17-PadA)") (class "Default")
      (node (ref "D17") (pin "A") (pinfunction "A_A") (pintype "passive"))
      (node (ref "R41") (pin "2") (pinfunction "2_2") (pintype "passive"))
    )
    (net (code "59") (name "Net-(D19-A)") (class "Default")
      (node (ref "C41") (pin "2") (pinfunction "2_2") (pintype "passive"))
      (node (ref "D19") (pin "2") (pinfunction "A_2") (pintype "passive"))
      (node (ref "L8") (pin "1") (pinfunction "P$1_1") (pintype "bidirectional"))
      (node (ref "Q6") (pin "D") (pinfunction "D_D") (pintype "passive"))
      (node (ref "TR3") (pin "P1_DOT") (pinfunction "P_DOT_P1_DOT") (pintype "passive"))
    )
    (net (code "60") (name "Net-(D20-PadC)") (class "Default")
      (node (ref "D20") (pin "C") (pinfunction "C_C") (pintype "passive"))
      (node (ref "Q5") (pin "G") (pinfunction "G_G") (pintype "passive"))
      (node (ref "R49") (pin "1") (pinfunction "1_1") (pintype "passive"))
    )
    (net (code "61") (name "Net-(D21-PadC)") (class "Default")
      (node (ref "D21") (pin "C") (pinfunction "C_C") (pintype "passive"))
      (node (ref "R54") (pin "1") (pinfunction "1_1") (pintype "passive"))
      (node (ref "R55") (pin "1") (pinfunction "1_1") (pintype "passive"))
    )
    (net (code "62") (name "Net-(D22-PadC)") (class "Default")
      (node (ref "D22") (pin "C") (pinfunction "C_C") (pintype "passive"))
      (node (ref "Q6") (pin "G") (pinfunction "G_G") (pintype "passive"))
      (node (ref "R53") (pin "1") (pinfunction "1_1") (pintype "passive"))
    )
    (net (code "63") (name "Net-(D23-PadC)") (class "Default")
      (node (ref "D23") (pin "C") (pinfunction "C_C") (pintype "passive"))
      (node (ref "D25") (pin "C") (pinfunction "C_C") (pintype "passive"))
      (node (ref "R51") (pin "2") (pinfunction "2_2") (pintype "passive"))
      (node (ref "R61") (pin "1") (pinfunction "1_1") (pintype "passive"))
    )
    (net (code "64") (name "Net-(IC1-BR)") (class "Default")
      (node (ref "IC1") (pin "8") (pinfunction "BR_8") (pintype "input"))
      (node (ref "R13") (pin "2") (pinfunction "2_2") (pintype "passive"))
      (node (ref "R19") (pin "1") (pinfunction "1_1") (pintype "passive"))
    )
    (net (code "65") (name "Net-(IC1-FB)") (class "Default")
      (node (ref "C26") (pin "2") (pinfunction "2_2") (pintype "passive"))
      (node (ref "C28") (pin "1") (pinfunction "1_1") (pintype "passive"))
      (node (ref "IC1") (pin "7") (pinfunction "FB_7") (pintype "input"))
      (node (ref "OK1") (pin "4") (pinfunction "COL_4") (pintype "passive"))
    )
    (net (code "66") (name "Net-(IC1-ZCD)") (class "Default")
      (node (ref "C27") (pin "1") (pinfunction "1_1") (pintype "passive"))
      (node (ref "IC1") (pin "6") (pinfunction "ZCD_6") (pintype "input"))
      (node (ref "R15") (pin "1") (pinfunction "1_1") (pintype "passive"))
      (node (ref "R16") (pin "1") (pinfunction "1_1") (pintype "passive"))
      (node (ref "R18") (pin "2") (pinfunction "2_2") (pintype "passive"))
    )
    (net (code "67") (name "Net-(IC2-DT)") (class "Default")
      (node (ref "IC2") (pin "6") (pinfunction "DT_6") (pintype "input"))
      (node (ref "R33") (pin "2") (pinfunction "2_2") (pintype "passive"))
    )
    (net (code "68") (name "Net-(IC2-VDDA)") (class "Default")
      (node (ref "C31") (pin "1") (pinfunction "1_1") (pintype "passive"))
      (node (ref "C32") (pin "1") (pinfunction "1_1") (pintype "passive"))
      (node (ref "C33") (pin "1") (pinfunction "1_1") (pintype "passive"))
      (node (ref "D10") (pin "1") (pinfunction "C_1") (pintype "passive"))
      (node (ref "D10") (pin "3") (pinfunction "C_3") (pintype "passive"))
      (node (ref "IC2") (pin "16") (pinfunction "VDDA_16") (pintype "power_in"))
    )
    (net (code "69") (name "Net-(IC2-VDDB)") (class "Default")
      (node (ref "C38") (pin "1") (pinfunction "1_1") (pintype "passive"))
      (node (ref "C39") (pin "1") (pinfunction "1_1") (pintype "passive"))
      (node (ref "C40") (pin "1") (pinfunction "1_1") (pintype "passive"))
      (node (ref "D13") (pin "C") (pinfunction "C_C") (pintype "passive"))
      (node (ref "IC2") (pin "11") (pinfunction "VDDB_11") (pintype "power_in"))
    )
    (net (code "70") (name "Net-(IC2-VIA)") (class "Default")
      (node (ref "IC2") (pin "1") (pinfunction "VIA_1") (pintype "input"))
      (node (ref "R28") (pin "1") (pinfunction "1_1") (pintype "passive"))
    )
    (net (code "71") (name "Net-(IC2-VIB)") (class "Default")
      (node (ref "IC2") (pin "2") (pinfunction "VIB_2") (pintype "input"))
      (node (ref "R29") (pin "1") (pinfunction "1_1") (pintype "passive"))
    )
    (net (code "72") (name "Net-(IC3-CS)") (class "Default")
      (node (ref "C49") (pin "2") (pinfunction "2_2") (pintype "passive"))
      (node (ref "IC3") (pin "12") (pinfunction "CS_12") (pintype "input"))
      (node (ref "R54") (pin "2") (pinfunction "2_2") (pintype "passive"))
    )
    (net (code "73") (name "Net-(IC3-RT{slash}SYNC)") (class "Default")
      (node (ref "IC3") (pin "15") (pinfunction "RT/SYNC_15") (pintype "input"))
      (node (ref "R52") (pin "1") (pinfunction "1_1") (pintype "passive"))
    )
    (net (code "74") (name "Net-(IC3-SS)") (class "Default")
      (node (ref "C46") (pin "2") (pinfunction "2_2") (pintype "passive"))
      (node (ref "IC3") (pin "13") (pinfunction "SS_13") (pintype "passive"))
    )
    (net (code "75") (name "Net-(IC3-TIME)") (class "Default")
      (node (ref "IC3") (pin "14") (pinfunction "TIME_14") (pintype "input"))
      (node (ref "R50") (pin "1") (pinfunction "1_1") (pintype "passive"))
    )
    (net (code "76") (name "Net-(IC3-UVLO)") (class "Default")
      (node (ref "IC3") (pin "16") (pinfunction "UVLO_16") (pintype "input"))
      (node (ref "R44") (pin "1") (pinfunction "1_1") (pintype "passive"))
      (node (ref "ZD4") (pin "C") (pinfunction "C_C") (pintype "passive"))
    )
    (net (code "77") (name "Net-(IC3-VCC)") (class "Default")
      (node (ref "C44") (pin "1") (pinfunction "1_1") (pintype "passive"))
      (node (ref "C45") (pin "1") (pinfunction "1_1") (pintype "passive"))
      (node (ref "IC3") (pin "1") (pinfunction "VIN_1") (pintype "input"))
      (node (ref "IC3") (pin "7") (pinfunction "VCC_7") (pintype "power_in"))
      (node (ref "R45") (pin "1") (pinfunction "1_1") (pintype "passive"))
    )
    (net (code "78") (name "Net-(IC4A-+IN)") (class "Default")
      (node (ref "C56") (pin "2") (pinfunction "2_2") (pintype "passive"))
      (node (ref "IC4") (pin "3") (pinfunction "+IN_3") (pintype "input"))
      (node (ref "R60") (pin "2") (pinfunction "2_2") (pintype "passive"))
    )
    (net (code "79") (name "Net-(IC4A--IN)") (class "Default")
      (node (ref "C54") (pin "1") (pinfunction "1_1") (pintype "passive"))
      (node (ref "D24") (pin "C") (pinfunction "C_C") (pintype "passive"))
      (node (ref "IC4") (pin "2") (pinfunction "-IN_2") (pintype "input"))
      (node (ref "R59") (pin "1") (pinfunction "1_1") (pintype "passive"))
      (node (ref "R64") (pin "1") (pinfunction "1_1") (pintype "passive"))
    )
    (net (code "80") (name "Net-(IC4A-OUT)") (class "Default")
      (node (ref "D23") (pin "A") (pinfunction "A_A") (pintype "passive"))
      (node (ref "IC4") (pin "1") (pinfunction "OUT_1") (pintype "output"))
    )
    (net (code "81") (name "Net-(IC4B-+IN)") (class "Default")
      (node (ref "C55") (pin "2") (pinfunction "2_2") (pintype "passive"))
      (node (ref "IC4") (pin "5") (pinfunction "+IN_5") (pintype "input"))
      (node (ref "R63") (pin "1") (pinfunction "1_1") (pintype "passive"))
      (node (ref "X3") (pin "1") (pinfunction "1_1") (pintype "passive"))
    )
    (net (code "82") (name "Net-(IC4B--IN)") (class "Default")
      (node (ref "IC4") (pin "6") (pinfunction "-IN_6") (pintype "input"))
      (node (ref "R58") (pin "1") (pinfunction "1_1") (pintype "passive"))
      (node (ref "R62") (pin "1") (pinfunction "1_1") (pintype "passive"))
    )
    (net (code "83") (name "Net-(IC4B-OUT)") (class "Default")
      (node (ref "D25") (pin "A") (pinfunction "A_A") (pintype "passive"))
      (node (ref "IC4") (pin "7") (pinfunction "OUT_7") (pintype "output"))
    )
    (net (code "84") (name "Net-(IC5-GATE1)") (class "Default")
      (node (ref "D26") (pin "C") (pinfunction "C_C") (pintype "passive"))
      (node (ref "IC5") (pin "1") (pinfunction "GATE1_1") (pintype "output"))
      (node (ref "R70") (pin "2") (pinfunction "2_2") (pintype "passive"))
    )
    (net (code "85") (name "Net-(IC5-GATE2)") (class "Default")
      (node (ref "D27") (pin "C") (pinfunction "C_C") (pintype "passive"))
      (node (ref "IC5") (pin "8") (pinfunction "GATE2_8") (pintype "output"))
      (node (ref "R74") (pin "2") (pinfunction "2_2") (pintype "passive"))
    )
    (net (code "86") (name "Net-(IC5-MOT)") (class "Default")
      (node (ref "IC5") (pin "3") (pinfunction "MOT_3") (pintype "passive"))
      (node (ref "R73") (pin "1") (pinfunction "1_1") (pintype "passive"))
    )
    (net (code "87") (name "Net-(IC5-VCC)") (class "Default")
      (node (ref "C65") (pin "1") (pinfunction "1_1") (pintype "passive"))
      (node (ref "C66") (pin "1") (pinfunction "1_1") (pintype "passive"))
      (node (ref "IC5") (pin "2") (pinfunction "VCC_2") (pintype "power_in"))
      (node (ref "R72") (pin "2") (pinfunction "2_2") (pintype "passive"))
    )
    (net (code "88") (name "Net-(IC6A--IN)") (class "Default")
      (node (ref "C76") (pin "2") (pinfunction "2_2") (pintype "passive"))
      (node (ref "IC6") (pin "2") (pinfunction "-IN_2") (pintype "input"))
      (node (ref "R82") (pin "1") (pinfunction "1_1") (pintype "passive"))
      (node (ref "R85") (pin "2") (pinfunction "2_2") (pintype "passive"))
      (node (ref "R89") (pin "1") (pinfunction "1_1") (pintype "passive"))
    )
    (net (code "89") (name "Net-(IC6A-OUT)") (class "Default")
      (node (ref "C76") (pin "1") (pinfunction "1_1") (pintype "passive"))
      (node (ref "IC6") (pin "1") (pinfunction "OUT_1") (pintype "output"))
      (node (ref "R92") (pin "2") (pinfunction "2_2") (pintype "passive"))
    )
    (net (code "90") (name "Net-(IC6B--IN)") (class "Default")
      (node (ref "IC6") (pin "6") (pinfunction "-IN_6") (pintype "input"))
      (node (ref "R77") (pin "2") (pinfunction "2_2") (pintype "passive"))
      (node (ref "R81") (pin "1") (pinfunction "1_1") (pintype "passive"))
    )
    (net (code "91") (name "Net-(IC6B-OUT)") (class "Default")
      (node (ref "IC6") (pin "7") (pinfunction "OUT_7") (pintype "output"))
      (node (ref "R77") (pin "1") (pinfunction "1_1") (pintype "passive"))
      (node (ref "R82") (pin "2") (pinfunction "2_2") (pintype "passive"))
    )
    (net (code "92") (name "Net-(IC6C-V+)") (class "Default")
      (node (ref "C71") (pin "1") (pinfunction "1_1") (pintype "passive"))
      (node (ref "C73") (pin "1") (pinfunction "1_1") (pintype "passive"))
      (node (ref "IC6") (pin "8") (pinfunction "V+_8") (pintype "power_in"))
      (node (ref "IC7") (pin "8") (pinfunction "VCC+_8") (pintype "power_in"))
      (node (ref "JP6") (pin "2") (pinfunction "2_2") (pintype "passive"))
      (node (ref "R72") (pin "1") (pinfunction "1_1") (pintype "passive"))
      (node (ref "R87") (pin "2") (pinfunction "2_2") (pintype "passive"))
      (node (ref "R88") (pin "2") (pinfunction "2_2") (pintype "passive"))
    )
    (net (code "93") (name "Net-(IC6C-V-)") (class "Default")
      (node (ref "C75") (pin "1") (pinfunction "1_1") (pintype "passive"))
      (node (ref "IC6") (pin "4") (pinfunction "V-_4") (pintype "power_in"))
      (node (ref "JP7") (pin "1") (pinfunction "1_1") (pintype "passive"))
    )
    (net (code "94") (name "Net-(IC7A--IN1)") (class "Default")
      (node (ref "C74") (pin "2") (pinfunction "2_2") (pintype "passive"))
      (node (ref "IC7") (pin "2") (pinfunction "-IN1_2") (pintype "input"))
      (node (ref "R86") (pin "1") (pinfunction "1_1") (pintype "passive"))
      (node (ref "R90") (pin "1") (pinfunction "1_1") (pintype "passive"))
    )
    (net (code "95") (name "Net-(IC7A-OUT1)") (class "Default")
      (node (ref "C74") (pin "1") (pinfunction "1_1") (pintype "passive"))
      (node (ref "C77") (pin "1") (pinfunction "1_1") (pintype "passive"))
      (node (ref "IC7") (pin "1") (pinfunction "OUT1_1") (pintype "output"))
      (node (ref "OK3") (pin "2") (pinfunction "C_2") (pintype "passive"))
    )
    (net (code "96") (name "Net-(IC7B-+IN)") (class "Default")
      (node (ref "C80") (pin "1") (pinfunction "1_1") (pintype "passive"))
      (node (ref "IC7") (pin "5") (pinfunction "+IN_5") (pintype "input"))
      (node (ref "JP8") (pin "COM") (pinfunction "COM_COM") (pintype "passive"))
    )
    (net (code "97") (name "Net-(IC7B--IN)") (class "Default")
      (node (ref "IC7") (pin "6") (pinfunction "-IN_6") (pintype "input"))
      (node (ref "IC7") (pin "7") (pinfunction "OUT_7") (pintype "output"))
      (node (ref "R89") (pin "2") (pinfunction "2_2") (pintype "passive"))
    )
    (net (code "98") (name "Net-(JP8-PadNO)") (class "Default")
      (node (ref "JP8") (pin "NO") (pinfunction "NO_NO") (pintype "passive"))
      (node (ref "P1") (pin "S") (pinfunction "S_S") (pintype "passive"))
    )
    (net (code "99") (name "Net-(L1B-1)") (class "Default")
      (node (ref "B1") (pin "AC1") (pinfunction "AC1_AC1") (pintype "passive"))
      (node (ref "C3") (pin "1") (pinfunction "1_1") (pintype "passive"))
      (node (ref "C8") (pin "2") (pinfunction "2_2") (pintype "passive"))
      (node (ref "L1") (pin "3") (pinfunction "1_3") (pintype "passive"))
      (node (ref "SAR1") (pin "2") (pinfunction "P$2_2") (pintype "bidirectional"))
    )
    (net (code "100") (name "Net-(L3-2)") (class "Default")
      (node (ref "C14") (pin "1") (pinfunction "1_1") (pintype "passive"))
      (node (ref "C16") (pin "+") (pinfunction "+_+") (pintype "passive"))
      (node (ref "JP4") (pin "2") (pinfunction "2_2") (pintype "passive"))
      (node (ref "L3") (pin "P$2") (pinfunction "2_P$2") (pintype "passive"))
      (node (ref "R8") (pin "1") (pinfunction "1_1") (pintype "passive"))
      (node (ref "R9") (pin "1") (pinfunction "1_1") (pintype "passive"))
      (node (ref "TR1") (pin "1") (pinfunction "SHIELD_1") (pintype "passive"))
      (node (ref "TR1") (pin "2") (pinfunction "P_2") (pintype "passive"))
    )
    (net (code "101") (name "Net-(LED1A-A)") (class "Default")
      (node (ref "LED1") (pin "BA") (pinfunction "A_BA") (pintype "passive"))
      (node (ref "R78") (pin "2") (pinfunction "2_2") (pintype "passive"))
    )
    (net (code "102") (name "Net-(LED1B-A)") (class "Default")
      (node (ref "LED1") (pin "TA") (pinfunction "A_TA") (pintype "passive"))
      (node (ref "R79") (pin "2") (pinfunction "2_2") (pintype "passive"))
    )
    (net (code "103") (name "Net-(OK1-A)") (class "Default")
      (node (ref "OK1") (pin "1") (pinfunction "A_1") (pintype "passive"))
      (node (ref "R17") (pin "2") (pinfunction "2_2") (pintype "passive"))
    )
    (net (code "104") (name "Net-(OK1-C)") (class "Default")
      (node (ref "OK1") (pin "2") (pinfunction "C_2") (pintype "passive"))
      (node (ref "R21") (pin "1") (pinfunction "1_1") (pintype "passive"))
      (node (ref "ZD3") (pin "C") (pinfunction "C_C") (pintype "passive"))
    )
    (net (code "105") (name "Net-(OK2-C)") (class "Default")
      (node (ref "OK2") (pin "2") (pinfunction "C_2") (pintype "passive"))
      (node (ref "R41") (pin "1") (pinfunction "1_1") (pintype "passive"))
    )
    (net (code "106") (name "Net-(OK3-A)") (class "Default")
      (node (ref "OK3") (pin "1") (pinfunction "A_1") (pintype "passive"))
      (node (ref "R88") (pin "1") (pinfunction "1_1") (pintype "passive"))
    )
    (net (code "107") (name "Net-(OK3-COL)") (class "Default")
      (node (ref "JP9") (pin "2") (pinfunction "2_2") (pintype "passive"))
      (node (ref "OK3") (pin "4") (pinfunction "COL_4") (pintype "passive"))
    )
    (net (code "108") (name "Net-(Q4-A)") (class "Default")
      (node (ref "D17") (pin "C") (pinfunction "C_C") (pintype "passive"))
      (node (ref "D18") (pin "C") (pinfunction "C_C") (pintype "passive"))
      (node (ref "Q4") (pin "3") (pinfunction "A_3") (pintype "passive"))
    )
    (net (code "109") (name "Net-(Q4-G)") (class "Default")
      (node (ref "C47") (pin "1") (pinfunction "1_1") (pintype "passive"))
      (node (ref "Q4") (pin "2") (pinfunction "G_2") (pintype "passive"))
      (node (ref "R51") (pin "1") (pinfunction "1_1") (pintype "passive"))
    )
    (net (code "110") (name "Net-(Q10-PadB)") (class "Default")
      (node (ref "Q10") (pin "B") (pinfunction "B_B") (pintype "passive"))
      (node (ref "R95") (pin "2") (pinfunction "2_2") (pintype "passive"))
      (node (ref "R96") (pin "1") (pinfunction "1_1") (pintype "passive"))
    )
    (net (code "111") (name "Net-(Q10-PadC)") (class "Default")
      (node (ref "Q10") (pin "C") (pinfunction "C_C") (pintype "passive"))
      (node (ref "Q9") (pin "B") (pinfunction "B_B") (pintype "passive"))
      (node (ref "R94") (pin "1") (pinfunction "1_1") (pintype "passive"))
    )
    (net (code "112") (name "Net-(Q10-PadE)") (class "Default")
      (node (ref "Q10") (pin "E") (pinfunction "E_E") (pintype "passive"))
      (node (ref "R93") (pin "2") (pinfunction "2_2") (pintype "passive"))
    )
    (net (code "113") (name "Net-(R2-Pad2)") (class "Default")
      (node (ref "R2") (pin "2") (pinfunction "2_2") (pintype "passive"))
      (node (ref "R3") (pin "1") (pinfunction "1_1") (pintype "passive"))
    )
    (net (code "114") (name "Net-(R12-Pad1)") (class "Default")
      (node (ref "R12") (pin "1") (pinfunction "1_1") (pintype "passive"))
      (node (ref "R8") (pin "2") (pinfunction "2_2") (pintype "passive"))
    )
    (net (code "115") (name "Net-(R12-Pad2)") (class "Default")
      (node (ref "R12") (pin "2") (pinfunction "2_2") (pintype "passive"))
      (node (ref "R13") (pin "1") (pinfunction "1_1") (pintype "passive"))
    )
    (net (code "116") (name "Net-(R22-Pad2)") (class "Default")
      (node (ref "R22") (pin "2") (pinfunction "2_2") (pintype "passive"))
      (node (ref "R27") (pin "1") (pinfunction "1_1") (pintype "passive"))
    )
    (net (code "117") (name "Net-(R27-Pad2)") (class "Default")
      (node (ref "R27") (pin "2") (pinfunction "2_2") (pintype "passive"))
      (node (ref "R31") (pin "1") (pinfunction "1_1") (pintype "passive"))
      (node (ref "TP2") (pin "1") (pinfunction "1_1") (pintype "passive"))
    )
    (net (code "118") (name "Net-(R30-Pad1)") (class "Default")
      (node (ref "R30") (pin "1") (pinfunction "1_1") (pintype "passive"))
      (node (ref "R32") (pin "2") (pinfunction "2_2") (pintype "passive"))
    )
    (net (code "119") (name "Net-(R47-Pad2)") (class "Default")
      (node (ref "R47") (pin "2") (pinfunction "2_2") (pintype "passive"))
      (node (ref "R48") (pin "1") (pinfunction "1_1") (pintype "passive"))
    )
    (net (code "120") (name "Net-(R80-Pad1)") (class "Default")
      (node (ref "R80") (pin "1") (pinfunction "1_1") (pintype "passive"))
      (node (ref "R84") (pin "2") (pinfunction "2_2") (pintype "passive"))
    )
    (net (code "121") (name "Net-(R83-Pad1)") (class "Default")
      (node (ref "R83") (pin "1") (pinfunction "1_1") (pintype "passive"))
      (node (ref "R84") (pin "1") (pinfunction "1_1") (pintype "passive"))
      (node (ref "R90") (pin "2") (pinfunction "2_2") (pintype "passive"))
      (node (ref "R91") (pin "2") (pinfunction "2_2") (pintype "passive"))
    )
    (net (code "122") (name "Net-(R96-Pad2)") (class "Default")
      (node (ref "R96") (pin "2") (pinfunction "2_2") (pintype "passive"))
      (node (ref "R97") (pin "1") (pinfunction "1_1") (pintype "passive"))
      (node (ref "R98") (pin "1") (pinfunction "1_1") (pintype "passive"))
    )
    (net (code "123") (name "Net-(SAR2-P$2)") (class "Default")
      (node (ref "B1") (pin "AC2") (pinfunction "AC2_AC2") (pintype "passive"))
      (node (ref "C3") (pin "2") (pinfunction "2_2") (pintype "passive"))
      (node (ref "C7") (pin "2") (pinfunction "2_2") (pintype "passive"))
      (node (ref "L1") (pin "1") (pinfunction "1_1") (pintype "passive"))
      (node (ref "SAR2") (pin "2") (pinfunction "P$2_2") (pintype "bidirectional"))
    )
    (net (code "124") (name "Net-(TR1-6V_DOT)") (class "Default")
      (node (ref "C22") (pin "2") (pinfunction "2_2") (pintype "passive"))
      (node (ref "D6") (pin "A") (pinfunction "A_A") (pintype "passive"))
      (node (ref "TR1") (pin "12") (pinfunction "6V_DOT_12") (pintype "passive"))
    )
    (net (code "125") (name "Net-(TR1-7V)") (class "Default")
      (node (ref "C17") (pin "2") (pinfunction "2_2") (pintype "passive"))
      (node (ref "D5") (pin "C") (pinfunction "C_C") (pintype "passive"))
      (node (ref "TR1") (pin "9") (pinfunction "7V_9") (pintype "passive"))
    )
    (net (code "126") (name "Net-(TR1-12V)") (class "Default")
      (node (ref "C15") (pin "2") (pinfunction "2_2") (pintype "passive"))
      (node (ref "D3") (pin "C") (pinfunction "C_C") (pintype "passive"))
      (node (ref "TR1") (pin "13") (pinfunction "12V_13") (pintype "passive"))
    )
    (net (code "127") (name "Net-(TR1-12V_DOT2)") (class "Default")
      (node (ref "C9") (pin "2") (pinfunction "2_2") (pintype "passive"))
      (node (ref "D2") (pin "A") (pinfunction "A_A") (pintype "passive"))
      (node (ref "TR1") (pin "15") (pinfunction "12V_DOT2_15") (pintype "passive"))
    )
    (net (code "128") (name "Net-(TR1-P2_DOT)") (class "Default")
      (node (ref "D4") (pin "A") (pinfunction "A_A") (pintype "passive"))
      (node (ref "IC1") (pin "13") (pinfunction "DRAIN_13") (pintype "output"))
      (node (ref "IC1") (pin "14") (pinfunction "DRAIN_14") (pintype "output"))
      (node (ref "IC1") (pin "15") (pinfunction "DRAIN_15") (pintype "output"))
      (node (ref "IC1") (pin "16") (pinfunction "DRAIN_16") (pintype "output"))
      (node (ref "TR1") (pin "4") (pinfunction "P2_DOT_4") (pintype "passive"))
    )
    (net (code "129") (name "Net-(TR2-P_DOT)") (class "Default")
      (node (ref "Q2") (pin "D") (pinfunction "D_D") (pintype "passive"))
      (node (ref "TR2") (pin "8") (pinfunction "P_DOT_8") (pintype "passive"))
    )
    (net (code "130") (name "Net-(X2C-1)") (class "Default")
      (node (ref "C13") (pin "2") (pinfunction "2_2") (pintype "passive"))
      (node (ref "L4") (pin "2") (pinfunction "2_2") (pintype "passive"))
      (node (ref "R7") (pin "2") (pinfunction "2_2") (pintype "passive"))
      (node (ref "X2") (pin "3") (pinfunction "1_3") (pintype "passive"))
    )
    (net (code "131") (name "Net-(X2E-1)") (class "Default")
      (node (ref "JP8") (pin "NC") (pinfunction "NC_NC") (pintype "passive"))
      (node (ref "X2") (pin "5") (pinfunction "1_5") (pintype "passive"))
    )
    (net (code "132") (name "Net-(X2F-1)") (class "Default")
      (node (ref "D28") (pin "A") (pinfunction "A_A") (pintype "passive"))
      (node (ref "X2") (pin "6") (pinfunction "1_6") (pintype "passive"))
    )
    (net (code "133") (name "PE") (class "Default")
      (node (ref "C4A") (pin "1") (pinfunction "1_1") (pintype "passive"))
      (node (ref "C5A") (pin "1") (pinfunction "1_1") (pintype "passive"))
      (node (ref "C67") (pin "2") (pinfunction "2_2") (pintype "passive"))
      (node (ref "C68") (pin "2") (pinfunction "2_2") (pintype "passive"))
      (node (ref "C69") (pin "2") (pinfunction "2_2") (pintype "passive"))
      (node (ref "C7") (pin "1") (pinfunction "1_1") (pintype "passive"))
      (node (ref "C8") (pin "1") (pinfunction "1_1") (pintype "passive"))
      (node (ref "JP2") (pin "1") (pinfunction "1_1") (pintype "passive"))
      (node (ref "JP5") (pin "NC") (pinfunction "NC_NC") (pintype "passive"))
      (node (ref "X1") (pin "3") (pinfunction "1_3") (pintype "passive"))
    )
    (net (code "134") (name "POUT+") (class "Default")
      (node (ref "C57") (pin "+") (pinfunction "+_+") (pintype "passive"))
      (node (ref "C58") (pin "+") (pinfunction "+_+") (pintype "passive"))
      (node (ref "C59") (pin "1") (pinfunction "1_1") (pintype "passive"))
      (node (ref "C67") (pin "1") (pinfunction "1_1") (pintype "passive"))
      (node (ref "L9") (pin "1") (pinfunction "1_1") (pintype "passive"))
      (node (ref "R66") (pin "1") (pinfunction "1_1") (pintype "passive"))
      (node (ref "SH3") (pin "P$2") (pinfunction "GND_B_P$2") (pintype "bidirectional"))
      (node (ref "SH4") (pin "P$1") (pinfunction "GND_A_P$1") (pintype "bidirectional"))
    )
    (net (code "135") (name "PREG_OUT+") (class "Default")
      (node (ref "C60") (pin "+") (pinfunction "+_+") (pintype "passive"))
      (node (ref "C61") (pin "1") (pinfunction "1_1") (pintype "passive"))
      (node (ref "C62") (pin "1") (pinfunction "1_1") (pintype "passive"))
      (node (ref "C68") (pin "1") (pinfunction "1_1") (pintype "passive"))
      (node (ref "C72") (pin "1") (pinfunction "1_1") (pintype "passive"))
      (node (ref "JP3") (pin "1") (pinfunction "1_1") (pintype "passive"))
      (node (ref "L9") (pin "2") (pinfunction "2_2") (pintype "passive"))
      (node (ref "R66") (pin "2") (pinfunction "2_2") (pintype "passive"))
      (node (ref "R67") (pin "2") (pinfunction "2_2") (pintype "passive"))
      (node (ref "R71") (pin "2") (pinfunction "2_2") (pintype "passive"))
      (node (ref "R80") (pin "2") (pinfunction "2_2") (pintype "passive"))
      (node (ref "TP6") (pin "TIP") (pinfunction "TIP_TIP") (pintype "bidirectional"))
      (node (ref "X4") (pin "1") (pinfunction "1_1") (pintype "passive"))
      (node (ref "ZD5") (pin "C") (pinfunction "C_C") (pintype "passive"))
    )
    (net (code "136") (name "PULL") (class "Default")
      (node (ref "D22") (pin "A") (pinfunction "A_A") (pintype "passive"))
      (node (ref "IC3") (pin "9") (pinfunction "PULL_9") (pintype "output"))
      (node (ref "R53") (pin "2") (pinfunction "2_2") (pintype "passive"))
    )
    (net (code "137") (name "PUSH") (class "Default")
      (node (ref "D20") (pin "A") (pinfunction "A_A") (pintype "passive"))
      (node (ref "IC3") (pin "8") (pinfunction "PUSH_8") (pintype "output"))
      (node (ref "R49") (pin "2") (pinfunction "2_2") (pintype "passive"))
    )
    (net (code "138") (name "REF") (class "Default")
      (node (ref "C37") (pin "2") (pinfunction "2_2") (pintype "passive"))
      (node (ref "IC2") (pin "3") (pinfunction "VDDI_3") (pintype "power_in"))
      (node (ref "IC2") (pin "8") (pinfunction "VDDI_8") (pintype "power_in"))
      (node (ref "R43") (pin "2") (pinfunction "2_2") (pintype "passive"))
    )
    (net (code "139") (name "S1_DOT_OUT") (class "Default")
      (node (ref "IC5") (pin "4") (pinfunction "VD1_4") (pintype "passive"))
      (node (ref "Q7") (pin "3") (pinfunction "D_3") (pintype "passive"))
      (node (ref "R68") (pin "1") (pinfunction "1_1") (pintype "passive"))
      (node (ref "R69") (pin "1") (pinfunction "1_1") (pintype "passive"))
      (node (ref "TR3") (pin "S1_DOT") (pinfunction "S1_DOT_S1_DOT") (pintype "passive"))
    )
    (net (code "140") (name "S1_OUT") (class "Default")
      (node (ref "SH3") (pin "P$1") (pinfunction "GND_A_P$1") (pintype "bidirectional"))
      (node (ref "TR3") (pin "S1") (pinfunction "S1_S1") (pintype "passive"))
    )
    (net (code "141") (name "S2_DOT_OUT") (class "Default")
      (node (ref "SH4") (pin "P$2") (pinfunction "GND_B_P$2") (pintype "bidirectional"))
      (node (ref "TR3") (pin "S2_DOT") (pinfunction "S2_DOT_S2_DOT") (pintype "passive"))
    )
    (net (code "142") (name "S2_OUT") (class "Default")
      (node (ref "IC5") (pin "5") (pinfunction "VD2_5") (pintype "passive"))
      (node (ref "Q8") (pin "3") (pinfunction "D_3") (pintype "passive"))
      (node (ref "R75") (pin "1") (pinfunction "1_1") (pintype "passive"))
      (node (ref "R76") (pin "1") (pinfunction "1_1") (pintype "passive"))
      (node (ref "TR3") (pin "S2") (pinfunction "S2_S2") (pintype "passive"))
    )
    (net (code "143") (name "SR_OUT1") (class "Default")
      (node (ref "D26") (pin "A") (pinfunction "A_A") (pintype "passive"))
      (node (ref "Q7") (pin "1") (pinfunction "G_1") (pintype "passive"))
      (node (ref "R70") (pin "1") (pinfunction "1_1") (pintype "passive"))
    )
    (net (code "144") (name "SR_OUT2") (class "Default")
      (node (ref "D27") (pin "A") (pinfunction "A_A") (pintype "passive"))
      (node (ref "Q8") (pin "1") (pinfunction "G_1") (pintype "passive"))
      (node (ref "R74") (pin "1") (pinfunction "1_1") (pintype "passive"))
    )
    (net (code "145") (name "UVLO") (class "Default")
      (node (ref "C43") (pin "1") (pinfunction "1_1") (pintype "passive"))
      (node (ref "D18") (pin "A") (pinfunction "A_A") (pintype "passive"))
      (node (ref "R31") (pin "2") (pinfunction "2_2") (pintype "passive"))
      (node (ref "R44") (pin "2") (pinfunction "2_2") (pintype "passive"))
      (node (ref "R46") (pin "1") (pinfunction "1_1") (pintype "passive"))
      (node (ref "R98") (pin "2") (pinfunction "2_2") (pintype "passive"))
      (node (ref "TP2") (pin "2") (pinfunction "2_2") (pintype "passive"))
    )
    (net (code "146") (name "V+") (class "Default")
      (node (ref "C25") (pin "1") (pinfunction "1_1") (pintype "passive"))
      (node (ref "JP6") (pin "1") (pinfunction "1_1") (pintype "passive"))
      (node (ref "L6") (pin "2") (pinfunction "2_2") (pintype "passive"))
      (node (ref "R21") (pin "2") (pinfunction "2_2") (pintype "passive"))
      (node (ref "R78") (pin "1") (pinfunction "1_1") (pintype "passive"))
      (node (ref "R79") (pin "1") (pinfunction "1_1") (pintype "passive"))
      (node (ref "X2") (pin "7") (pinfunction "1_7") (pintype "passive"))
    )
    (net (code "147") (name "V-") (class "Default")
      (node (ref "C19") (pin "2") (pinfunction "2_2") (pintype "passive"))
      (node (ref "JP7") (pin "2") (pinfunction "2_2") (pintype "passive"))
      (node (ref "L5") (pin "2") (pinfunction "2_2") (pintype "passive"))
      (node (ref "X2") (pin "9") (pinfunction "1_9") (pintype "passive"))
    )
    (net (code "148") (name "~{FAULT}") (class "Default")
      (node (ref "D28") (pin "C") (pinfunction "C_C") (pintype "passive"))
      (node (ref "LED1") (pin "BC") (pinfunction "C_BC") (pintype "passive"))
      (node (ref "OK2") (pin "4") (pinfunction "COL_4") (pintype "passive"))
    )
  )
)
